# fiberInterface_revC_V3.net
KiCad netlist of a schematic drawn in EAGLE
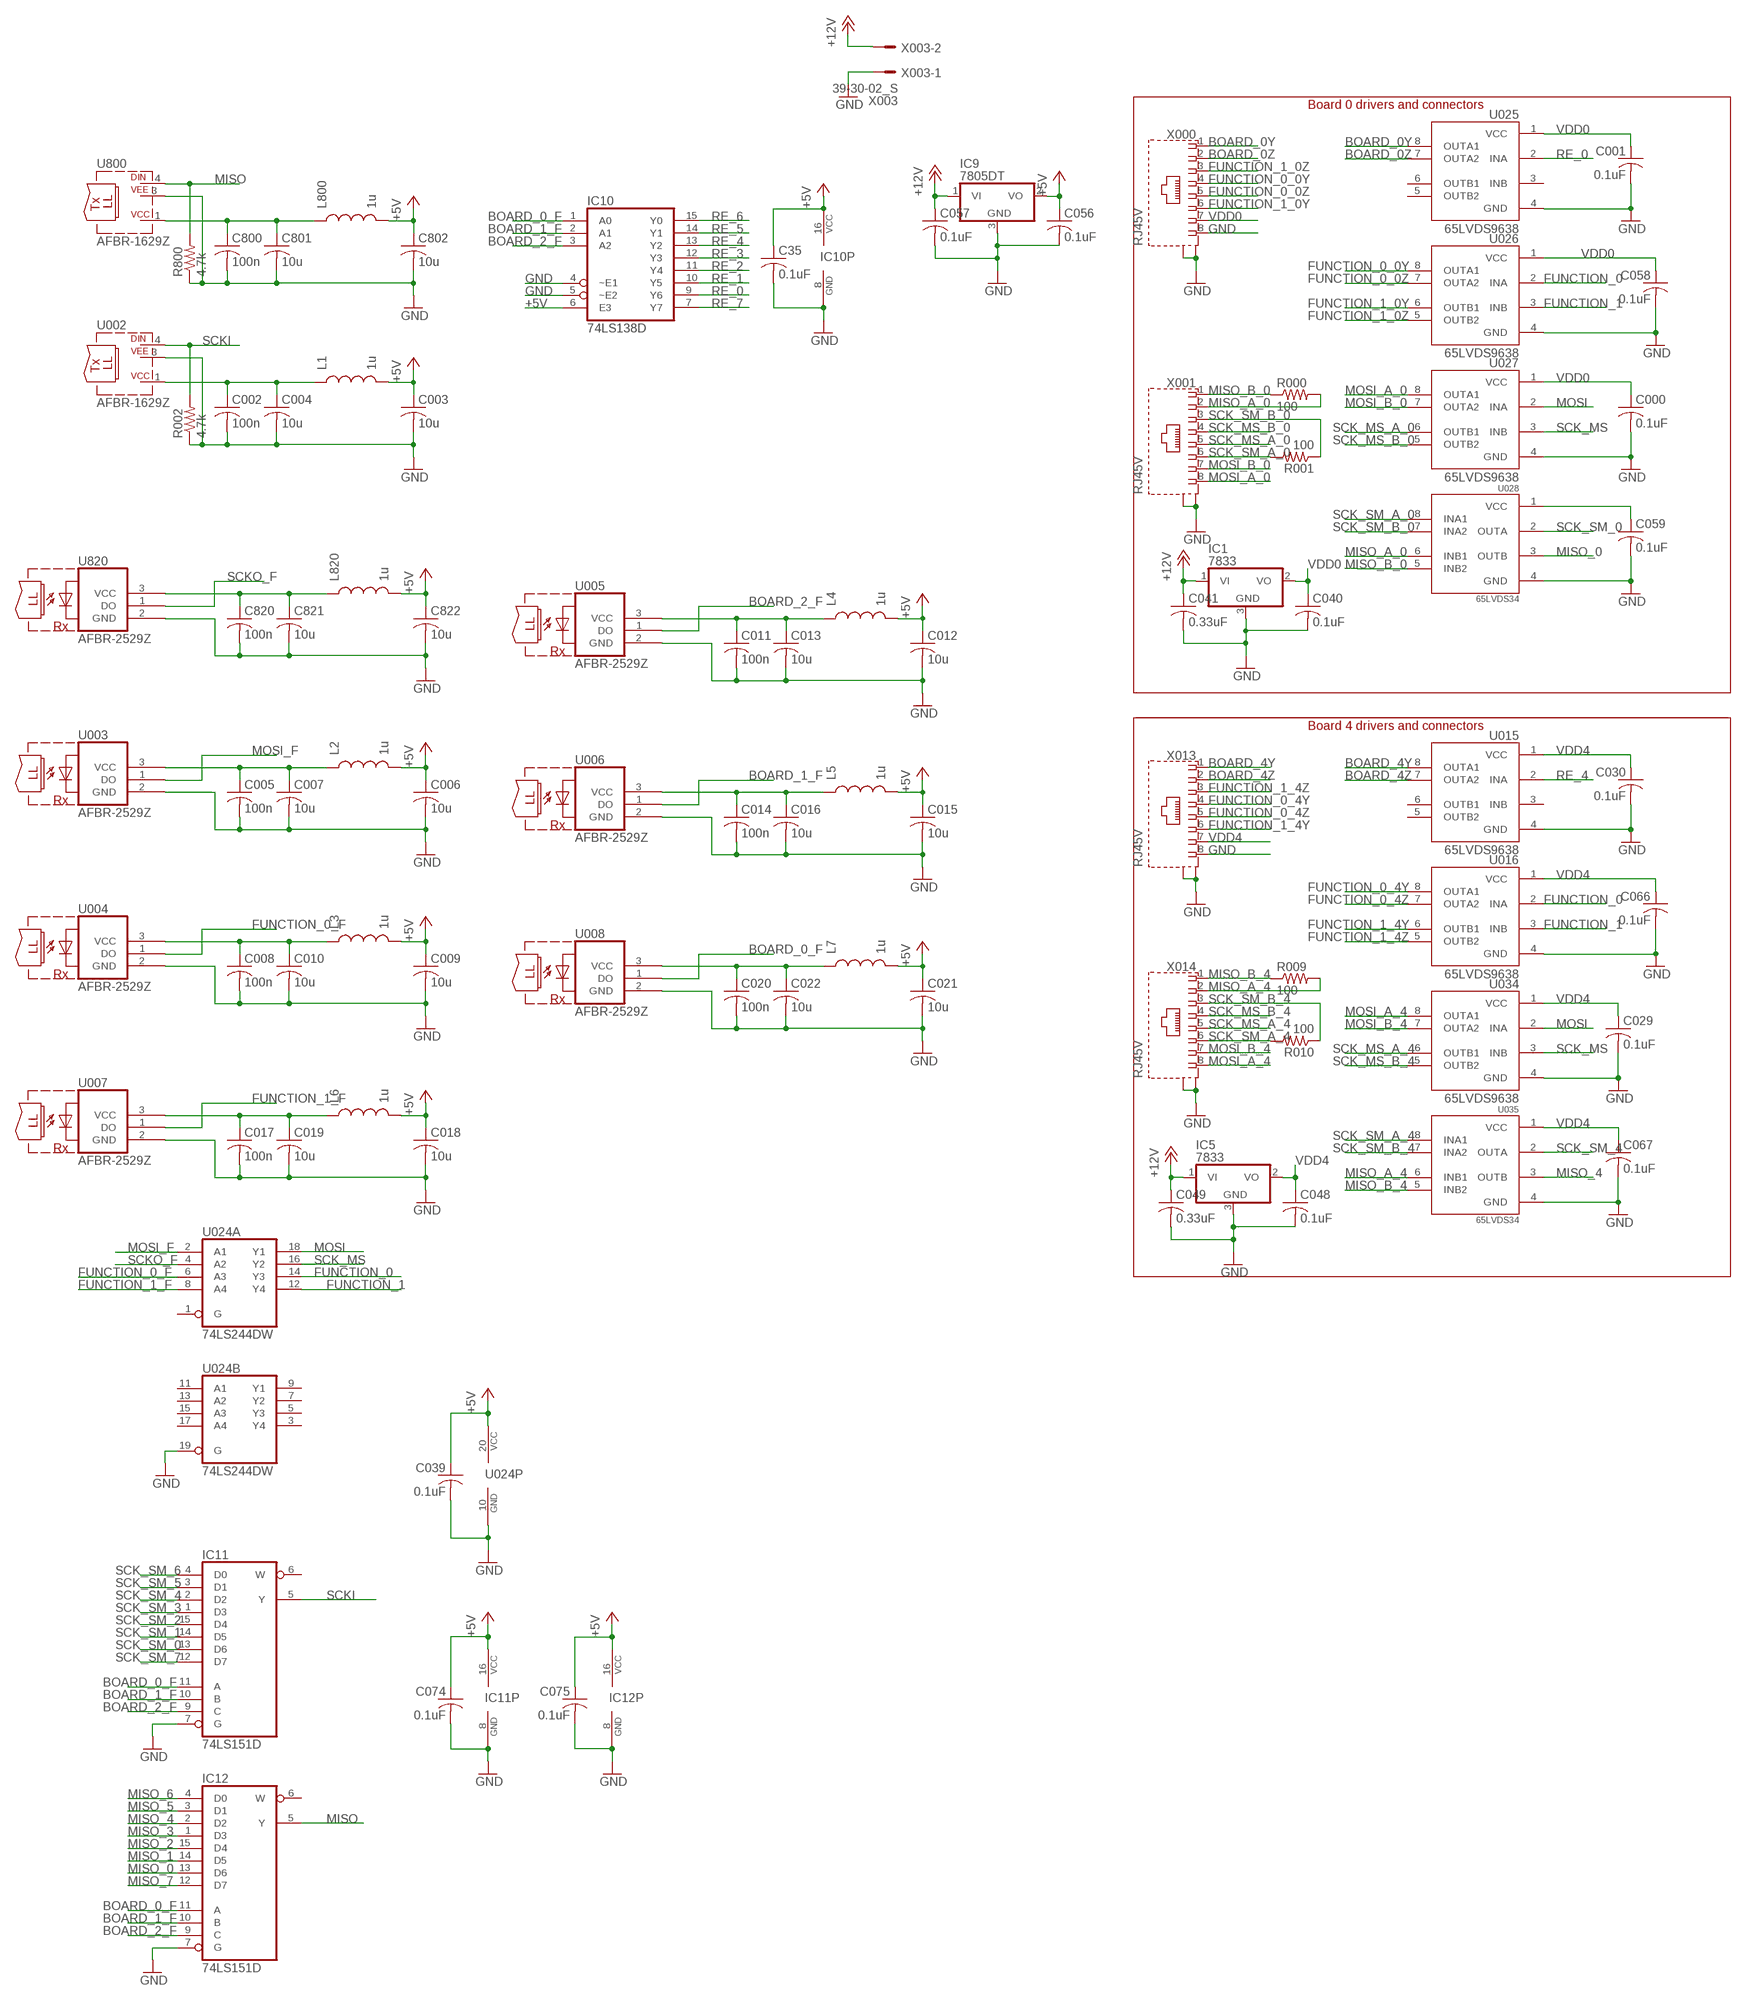
[diagram p0: schematic, sheet 1, part 1 of 2]
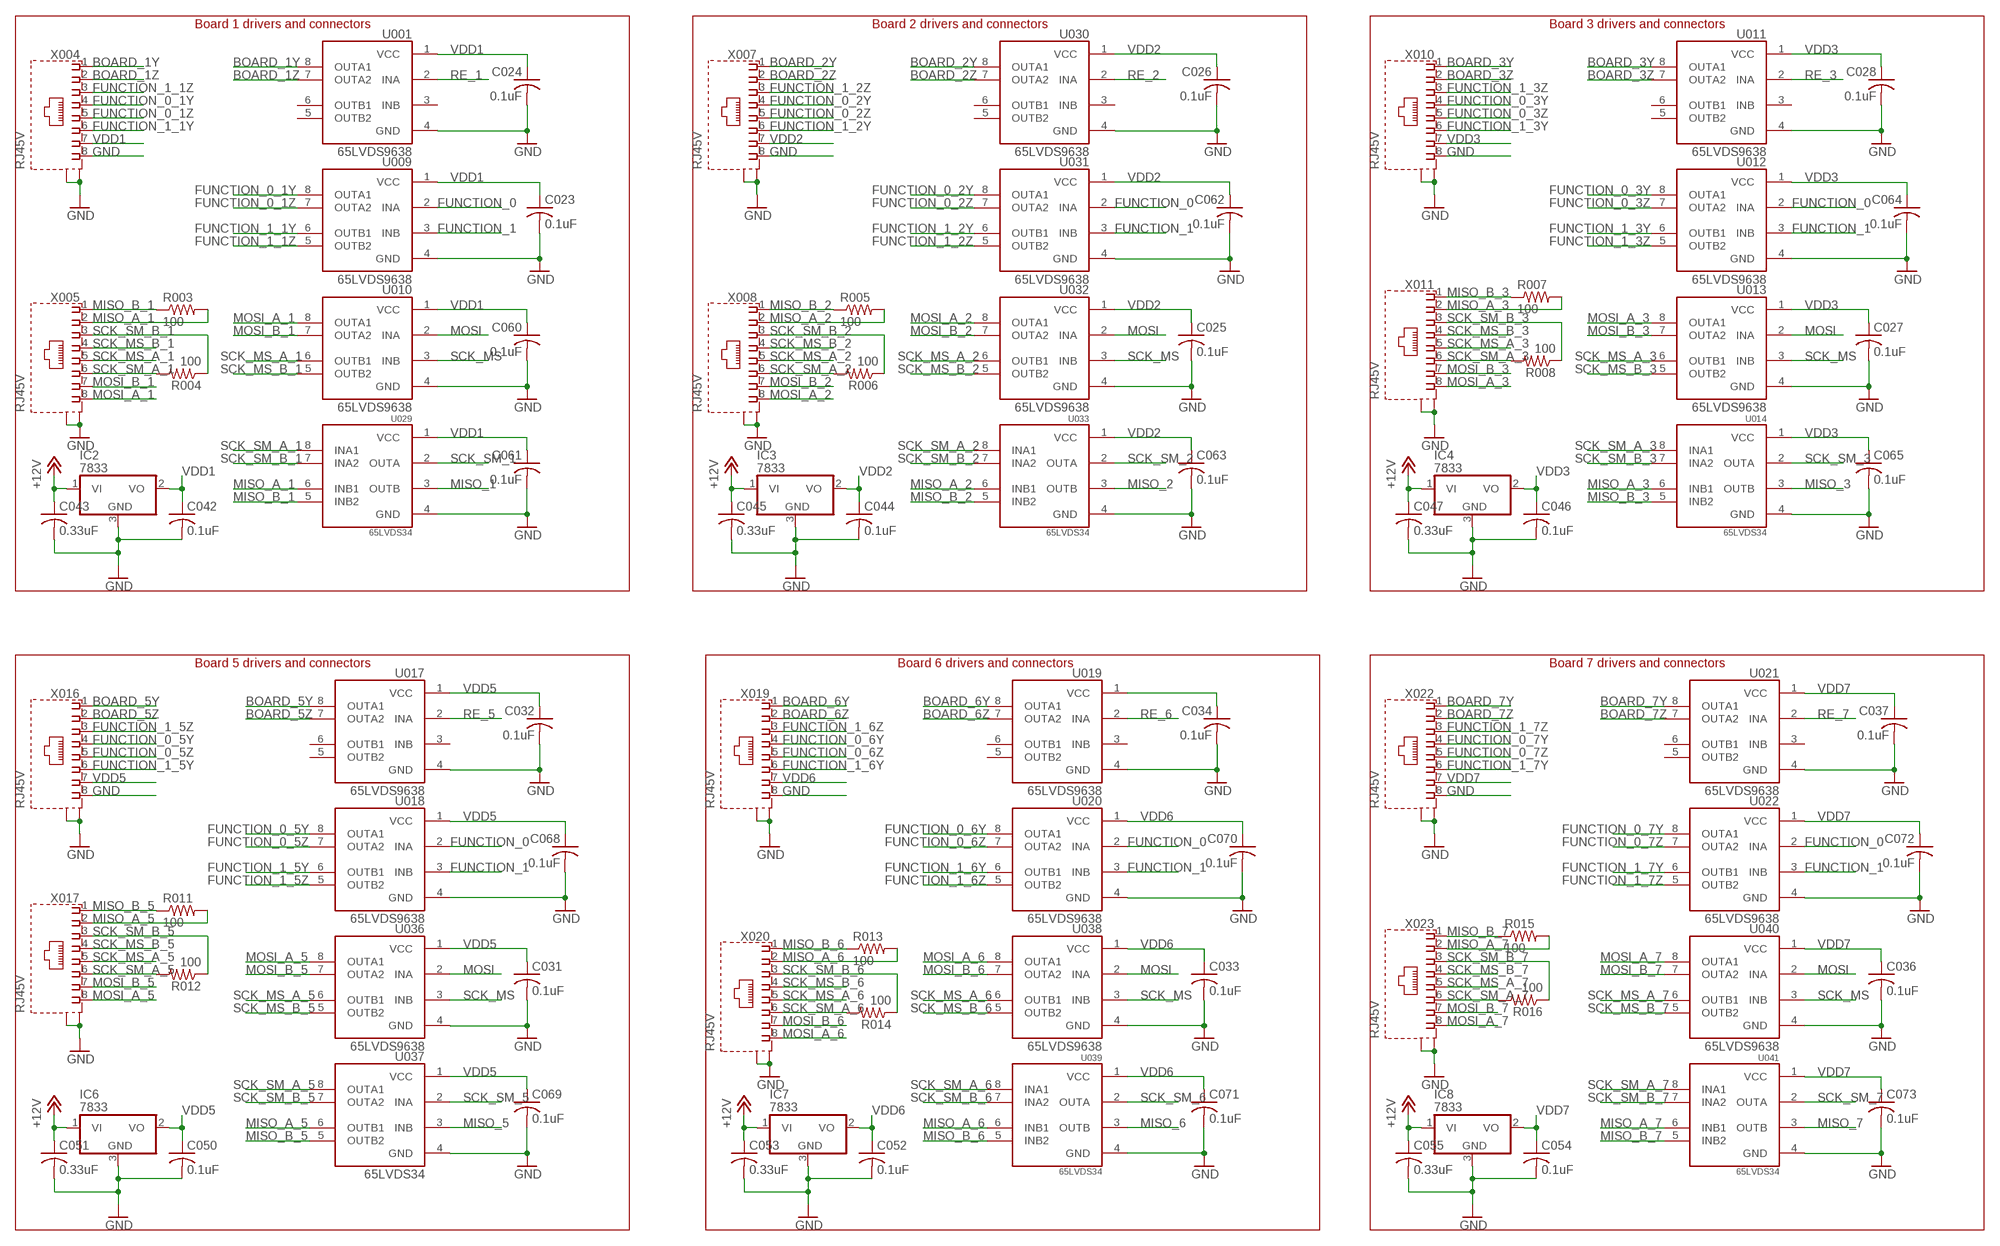
[diagram p1: schematic, sheet 1, part 2 of 2]

(export (version "E")
  (design (tool "Eeschema 10.0.6"))
  (components
    (comp (ref "C000")
      (value "0.1uF")
      (footprint "eagle-import:C0603")
      (libsource (lib "eagle-import") (part "C-USC0603"))
    )
    (comp (ref "C001")
      (value "0.1uF")
      (footprint "eagle-import:C0603")
      (libsource (lib "eagle-import") (part "C-USC0603"))
    )
    (comp (ref "C002")
      (value "100n")
      (footprint "eagle-import:C0805")
      (libsource (lib "eagle-import") (part "C-USC0805"))
    )
    (comp (ref "C003")
      (value "10u")
      (footprint "eagle-import:C1206")
      (libsource (lib "eagle-import") (part "C-USC1206"))
    )
    (comp (ref "C004")
      (value "10u")
      (footprint "eagle-import:C1206")
      (libsource (lib "eagle-import") (part "C-USC1206"))
    )
    (comp (ref "C005")
      (value "100n")
      (footprint "eagle-import:C0805")
      (libsource (lib "eagle-import") (part "C-USC0805"))
    )
    (comp (ref "C006")
      (value "10u")
      (footprint "eagle-import:C1206")
      (libsource (lib "eagle-import") (part "C-USC1206"))
    )
    (comp (ref "C007")
      (value "10u")
      (footprint "eagle-import:C1206")
      (libsource (lib "eagle-import") (part "C-USC1206"))
    )
    (comp (ref "C008")
      (value "100n")
      (footprint "eagle-import:C0805")
      (libsource (lib "eagle-import") (part "C-USC0805"))
    )
    (comp (ref "C009")
      (value "10u")
      (footprint "eagle-import:C1206")
      (libsource (lib "eagle-import") (part "C-USC1206"))
    )
    (comp (ref "C010")
      (value "10u")
      (footprint "eagle-import:C1206")
      (libsource (lib "eagle-import") (part "C-USC1206"))
    )
    (comp (ref "C011")
      (value "100n")
      (footprint "eagle-import:C0805")
      (libsource (lib "eagle-import") (part "C-USC0805"))
    )
    (comp (ref "C012")
      (value "10u")
      (footprint "eagle-import:C1206")
      (libsource (lib "eagle-import") (part "C-USC1206"))
    )
    (comp (ref "C013")
      (value "10u")
      (footprint "eagle-import:C1206")
      (libsource (lib "eagle-import") (part "C-USC1206"))
    )
    (comp (ref "C014")
      (value "100n")
      (footprint "eagle-import:C0805")
      (libsource (lib "eagle-import") (part "C-USC0805"))
    )
    (comp (ref "C015")
      (value "10u")
      (footprint "eagle-import:C1206")
      (libsource (lib "eagle-import") (part "C-USC1206"))
    )
    (comp (ref "C016")
      (value "10u")
      (footprint "eagle-import:C1206")
      (libsource (lib "eagle-import") (part "C-USC1206"))
    )
    (comp (ref "C017")
      (value "100n")
      (footprint "eagle-import:C0805")
      (libsource (lib "eagle-import") (part "C-USC0805"))
    )
    (comp (ref "C018")
      (value "10u")
      (footprint "eagle-import:C1206")
      (libsource (lib "eagle-import") (part "C-USC1206"))
    )
    (comp (ref "C019")
      (value "10u")
      (footprint "eagle-import:C1206")
      (libsource (lib "eagle-import") (part "C-USC1206"))
    )
    (comp (ref "C020")
      (value "100n")
      (footprint "eagle-import:C0805")
      (libsource (lib "eagle-import") (part "C-USC0805"))
    )
    (comp (ref "C021")
      (value "10u")
      (footprint "eagle-import:C1206")
      (libsource (lib "eagle-import") (part "C-USC1206"))
    )
    (comp (ref "C022")
      (value "10u")
      (footprint "eagle-import:C1206")
      (libsource (lib "eagle-import") (part "C-USC1206"))
    )
    (comp (ref "C023")
      (value "0.1uF")
      (footprint "eagle-import:C0603")
      (libsource (lib "eagle-import") (part "C-USC0603"))
    )
    (comp (ref "C024")
      (value "0.1uF")
      (footprint "eagle-import:C0603")
      (libsource (lib "eagle-import") (part "C-USC0603"))
    )
    (comp (ref "C025")
      (value "0.1uF")
      (footprint "eagle-import:C0603")
      (libsource (lib "eagle-import") (part "C-USC0603"))
    )
    (comp (ref "C026")
      (value "0.1uF")
      (footprint "eagle-import:C0603")
      (libsource (lib "eagle-import") (part "C-USC0603"))
    )
    (comp (ref "C027")
      (value "0.1uF")
      (footprint "eagle-import:C0603")
      (libsource (lib "eagle-import") (part "C-USC0603"))
    )
    (comp (ref "C028")
      (value "0.1uF")
      (footprint "eagle-import:C0603")
      (libsource (lib "eagle-import") (part "C-USC0603"))
    )
    (comp (ref "C029")
      (value "0.1uF")
      (footprint "eagle-import:C0603")
      (libsource (lib "eagle-import") (part "C-USC0603"))
    )
    (comp (ref "C030")
      (value "0.1uF")
      (footprint "eagle-import:C0603")
      (libsource (lib "eagle-import") (part "C-USC0603"))
    )
    (comp (ref "C031")
      (value "0.1uF")
      (footprint "eagle-import:C0603")
      (libsource (lib "eagle-import") (part "C-USC0603"))
    )
    (comp (ref "C032")
      (value "0.1uF")
      (footprint "eagle-import:C0603")
      (libsource (lib "eagle-import") (part "C-USC0603"))
    )
    (comp (ref "C033")
      (value "0.1uF")
      (footprint "eagle-import:C0603")
      (libsource (lib "eagle-import") (part "C-USC0603"))
    )
    (comp (ref "C034")
      (value "0.1uF")
      (footprint "eagle-import:C0603")
      (libsource (lib "eagle-import") (part "C-USC0603"))
    )
    (comp (ref "C35")
      (value "0.1uF")
      (footprint "eagle-import:C0603")
      (libsource (lib "eagle-import") (part "C-USC0603"))
    )
    (comp (ref "C036")
      (value "0.1uF")
      (footprint "eagle-import:C0603")
      (libsource (lib "eagle-import") (part "C-USC0603"))
    )
    (comp (ref "C037")
      (value "0.1uF")
      (footprint "eagle-import:C0603")
      (libsource (lib "eagle-import") (part "C-USC0603"))
    )
    (comp (ref "C039")
      (value "0.1uF")
      (footprint "eagle-import:C0603")
      (libsource (lib "eagle-import") (part "C-USC0603"))
    )
    (comp (ref "C040")
      (value "0.1uF")
      (footprint "eagle-import:C0805")
      (libsource (lib "eagle-import") (part "C-USC0805"))
    )
    (comp (ref "C041")
      (value "0.33uF")
      (footprint "eagle-import:C0805")
      (libsource (lib "eagle-import") (part "C-USC0805"))
    )
    (comp (ref "C042")
      (value "0.1uF")
      (footprint "eagle-import:C0805")
      (libsource (lib "eagle-import") (part "C-USC0805"))
    )
    (comp (ref "C043")
      (value "0.33uF")
      (footprint "eagle-import:C0805")
      (libsource (lib "eagle-import") (part "C-USC0805"))
    )
    (comp (ref "C044")
      (value "0.1uF")
      (footprint "eagle-import:C0805")
      (libsource (lib "eagle-import") (part "C-USC0805"))
    )
    (comp (ref "C045")
      (value "0.33uF")
      (footprint "eagle-import:C0805")
      (libsource (lib "eagle-import") (part "C-USC0805"))
    )
    (comp (ref "C046")
      (value "0.1uF")
      (footprint "eagle-import:C0805")
      (libsource (lib "eagle-import") (part "C-USC0805"))
    )
    (comp (ref "C047")
      (value "0.33uF")
      (footprint "eagle-import:C0805")
      (libsource (lib "eagle-import") (part "C-USC0805"))
    )
    (comp (ref "C048")
      (value "0.1uF")
      (footprint "eagle-import:C0805")
      (libsource (lib "eagle-import") (part "C-USC0805"))
    )
    (comp (ref "C049")
      (value "0.33uF")
      (footprint "eagle-import:C0805")
      (libsource (lib "eagle-import") (part "C-USC0805"))
    )
    (comp (ref "C050")
      (value "0.1uF")
      (footprint "eagle-import:C0805")
      (libsource (lib "eagle-import") (part "C-USC0805"))
    )
    (comp (ref "C051")
      (value "0.33uF")
      (footprint "eagle-import:C0805")
      (libsource (lib "eagle-import") (part "C-USC0805"))
    )
    (comp (ref "C052")
      (value "0.1uF")
      (footprint "eagle-import:C0805")
      (libsource (lib "eagle-import") (part "C-USC0805"))
    )
    (comp (ref "C053")
      (value "0.33uF")
      (footprint "eagle-import:C0805")
      (libsource (lib "eagle-import") (part "C-USC0805"))
    )
    (comp (ref "C054")
      (value "0.1uF")
      (footprint "eagle-import:C0805")
      (libsource (lib "eagle-import") (part "C-USC0805"))
    )
    (comp (ref "C055")
      (value "0.33uF")
      (footprint "eagle-import:C0805")
      (libsource (lib "eagle-import") (part "C-USC0805"))
    )
    (comp (ref "C056")
      (value "0.1uF")
      (footprint "eagle-import:C0603")
      (libsource (lib "eagle-import") (part "C-USC0603"))
    )
    (comp (ref "C057")
      (value "0.1uF")
      (footprint "eagle-import:C0603")
      (libsource (lib "eagle-import") (part "C-USC0603"))
    )
    (comp (ref "C058")
      (value "0.1uF")
      (footprint "eagle-import:C0603")
      (libsource (lib "eagle-import") (part "C-USC0603"))
    )
    (comp (ref "C059")
      (value "0.1uF")
      (footprint "eagle-import:C0603")
      (libsource (lib "eagle-import") (part "C-USC0603"))
    )
    (comp (ref "C060")
      (value "0.1uF")
      (footprint "eagle-import:C0603")
      (libsource (lib "eagle-import") (part "C-USC0603"))
    )
    (comp (ref "C061")
      (value "0.1uF")
      (footprint "eagle-import:C0603")
      (libsource (lib "eagle-import") (part "C-USC0603"))
    )
    (comp (ref "C062")
      (value "0.1uF")
      (footprint "eagle-import:C0603")
      (libsource (lib "eagle-import") (part "C-USC0603"))
    )
    (comp (ref "C063")
      (value "0.1uF")
      (footprint "eagle-import:C0603")
      (libsource (lib "eagle-import") (part "C-USC0603"))
    )
    (comp (ref "C064")
      (value "0.1uF")
      (footprint "eagle-import:C0603")
      (libsource (lib "eagle-import") (part "C-USC0603"))
    )
    (comp (ref "C065")
      (value "0.1uF")
      (footprint "eagle-import:C0603")
      (libsource (lib "eagle-import") (part "C-USC0603"))
    )
    (comp (ref "C066")
      (value "0.1uF")
      (footprint "eagle-import:C0603")
      (libsource (lib "eagle-import") (part "C-USC0603"))
    )
    (comp (ref "C067")
      (value "0.1uF")
      (footprint "eagle-import:C0603")
      (libsource (lib "eagle-import") (part "C-USC0603"))
    )
    (comp (ref "C068")
      (value "0.1uF")
      (footprint "eagle-import:C0603")
      (libsource (lib "eagle-import") (part "C-USC0603"))
    )
    (comp (ref "C069")
      (value "0.1uF")
      (footprint "eagle-import:C0603")
      (libsource (lib "eagle-import") (part "C-USC0603"))
    )
    (comp (ref "C070")
      (value "0.1uF")
      (footprint "eagle-import:C0603")
      (libsource (lib "eagle-import") (part "C-USC0603"))
    )
    (comp (ref "C071")
      (value "0.1uF")
      (footprint "eagle-import:C0603")
      (libsource (lib "eagle-import") (part "C-USC0603"))
    )
    (comp (ref "C072")
      (value "0.1uF")
      (footprint "eagle-import:C0603")
      (libsource (lib "eagle-import") (part "C-USC0603"))
    )
    (comp (ref "C073")
      (value "0.1uF")
      (footprint "eagle-import:C0603")
      (libsource (lib "eagle-import") (part "C-USC0603"))
    )
    (comp (ref "C074")
      (value "0.1uF")
      (footprint "eagle-import:C0603")
      (libsource (lib "eagle-import") (part "C-USC0603"))
    )
    (comp (ref "C075")
      (value "0.1uF")
      (footprint "eagle-import:C0603")
      (libsource (lib "eagle-import") (part "C-USC0603"))
    )
    (comp (ref "C800")
      (value "100n")
      (footprint "eagle-import:C0805")
      (libsource (lib "eagle-import") (part "C-USC0805"))
    )
    (comp (ref "C801")
      (value "10u")
      (footprint "eagle-import:C1206")
      (libsource (lib "eagle-import") (part "C-USC1206"))
    )
    (comp (ref "C802")
      (value "10u")
      (footprint "eagle-import:C1206")
      (libsource (lib "eagle-import") (part "C-USC1206"))
    )
    (comp (ref "C820")
      (value "100n")
      (footprint "eagle-import:C0805")
      (libsource (lib "eagle-import") (part "C-USC0805"))
    )
    (comp (ref "C821")
      (value "10u")
      (footprint "eagle-import:C1206")
      (libsource (lib "eagle-import") (part "C-USC1206"))
    )
    (comp (ref "C822")
      (value "10u")
      (footprint "eagle-import:C1206")
      (libsource (lib "eagle-import") (part "C-USC1206"))
    )
    (comp (ref "IC1")
      (value "7833")
      (footprint "eagle-import:TO252")
      (libsource (lib "eagle-import") (part "78DT05"))
    )
    (comp (ref "IC2")
      (value "7833")
      (footprint "eagle-import:TO252")
      (libsource (lib "eagle-import") (part "78DT05"))
    )
    (comp (ref "IC3")
      (value "7833")
      (footprint "eagle-import:TO252")
      (libsource (lib "eagle-import") (part "78DT05"))
    )
    (comp (ref "IC4")
      (value "7833")
      (footprint "eagle-import:TO252")
      (libsource (lib "eagle-import") (part "78DT05"))
    )
    (comp (ref "IC5")
      (value "7833")
      (footprint "eagle-import:TO252")
      (libsource (lib "eagle-import") (part "78DT05"))
    )
    (comp (ref "IC6")
      (value "7833")
      (footprint "eagle-import:TO252")
      (libsource (lib "eagle-import") (part "78DT05"))
    )
    (comp (ref "IC7")
      (value "7833")
      (footprint "eagle-import:TO252")
      (libsource (lib "eagle-import") (part "78DT05"))
    )
    (comp (ref "IC8")
      (value "7833")
      (footprint "eagle-import:TO252")
      (libsource (lib "eagle-import") (part "78DT05"))
    )
    (comp (ref "IC9")
      (value "7805DT")
      (footprint "eagle-import:TO252")
      (libsource (lib "eagle-import") (part "78DT05"))
    )
    (comp (ref "IC10")
      (value "74LS138D")
      (footprint "eagle-import:SO16")
      (libsource (lib "eagle-import") (part "74238DLS"))
    )
    (comp (ref "IC11")
      (value "74LS151D")
      (footprint "eagle-import:SO16")
      (libsource (lib "eagle-import") (part "74151DLS"))
    )
    (comp (ref "IC12")
      (value "74LS151D")
      (footprint "eagle-import:SO16")
      (libsource (lib "eagle-import") (part "74151DLS"))
    )
    (comp (ref "L1")
      (value "1u")
      (footprint "eagle-import:0805")
      (libsource (lib "eagle-import") (part "INDUCTOR0805"))
    )
    (comp (ref "L2")
      (value "1u")
      (footprint "eagle-import:0805")
      (libsource (lib "eagle-import") (part "INDUCTOR0805"))
    )
    (comp (ref "L3")
      (value "1u")
      (footprint "eagle-import:0805")
      (libsource (lib "eagle-import") (part "INDUCTOR0805"))
    )
    (comp (ref "L4")
      (value "1u")
      (footprint "eagle-import:0805")
      (libsource (lib "eagle-import") (part "INDUCTOR0805"))
    )
    (comp (ref "L5")
      (value "1u")
      (footprint "eagle-import:0805")
      (libsource (lib "eagle-import") (part "INDUCTOR0805"))
    )
    (comp (ref "L6")
      (value "1u")
      (footprint "eagle-import:0805")
      (libsource (lib "eagle-import") (part "INDUCTOR0805"))
    )
    (comp (ref "L7")
      (value "1u")
      (footprint "eagle-import:0805")
      (libsource (lib "eagle-import") (part "INDUCTOR0805"))
    )
    (comp (ref "L800")
      (value "1u")
      (footprint "eagle-import:0805")
      (libsource (lib "eagle-import") (part "INDUCTOR0805"))
    )
    (comp (ref "L820")
      (value "1u")
      (footprint "eagle-import:0805")
      (libsource (lib "eagle-import") (part "INDUCTOR0805"))
    )
    (comp (ref "R000")
      (value "100")
      (footprint "eagle-import:R0805")
      (libsource (lib "eagle-import") (part "R-US_R0805"))
    )
    (comp (ref "R001")
      (value "100")
      (footprint "eagle-import:R0805")
      (libsource (lib "eagle-import") (part "R-US_R0805"))
    )
    (comp (ref "R002")
      (value "4.7k")
      (footprint "eagle-import:R0805")
      (libsource (lib "eagle-import") (part "R-US_R0805"))
    )
    (comp (ref "R003")
      (value "100")
      (footprint "eagle-import:R0805")
      (libsource (lib "eagle-import") (part "R-US_R0805"))
    )
    (comp (ref "R004")
      (value "100")
      (footprint "eagle-import:R0805")
      (libsource (lib "eagle-import") (part "R-US_R0805"))
    )
    (comp (ref "R005")
      (value "100")
      (footprint "eagle-import:R0805")
      (libsource (lib "eagle-import") (part "R-US_R0805"))
    )
    (comp (ref "R006")
      (value "100")
      (footprint "eagle-import:R0805")
      (libsource (lib "eagle-import") (part "R-US_R0805"))
    )
    (comp (ref "R007")
      (value "100")
      (footprint "eagle-import:R0805")
      (libsource (lib "eagle-import") (part "R-US_R0805"))
    )
    (comp (ref "R008")
      (value "100")
      (footprint "eagle-import:R0805")
      (libsource (lib "eagle-import") (part "R-US_R0805"))
    )
    (comp (ref "R009")
      (value "100")
      (footprint "eagle-import:R0805")
      (libsource (lib "eagle-import") (part "R-US_R0805"))
    )
    (comp (ref "R010")
      (value "100")
      (footprint "eagle-import:R0805")
      (libsource (lib "eagle-import") (part "R-US_R0805"))
    )
    (comp (ref "R011")
      (value "100")
      (footprint "eagle-import:R0805")
      (libsource (lib "eagle-import") (part "R-US_R0805"))
    )
    (comp (ref "R012")
      (value "100")
      (footprint "eagle-import:R0805")
      (libsource (lib "eagle-import") (part "R-US_R0805"))
    )
    (comp (ref "R013")
      (value "100")
      (footprint "eagle-import:R0805")
      (libsource (lib "eagle-import") (part "R-US_R0805"))
    )
    (comp (ref "R014")
      (value "100")
      (footprint "eagle-import:R0805")
      (libsource (lib "eagle-import") (part "R-US_R0805"))
    )
    (comp (ref "R015")
      (value "100")
      (footprint "eagle-import:R0805")
      (libsource (lib "eagle-import") (part "R-US_R0805"))
    )
    (comp (ref "R016")
      (value "100")
      (footprint "eagle-import:R0805")
      (libsource (lib "eagle-import") (part "R-US_R0805"))
    )
    (comp (ref "R800")
      (value "4.7k")
      (footprint "eagle-import:R0805")
      (libsource (lib "eagle-import") (part "R-US_R0805"))
    )
    (comp (ref "U001")
      (value "65LVDS9638")
      (footprint "eagle-import:SO08-1")
      (libsource (lib "eagle-import") (part "DS9638"))
    )
    (comp (ref "U002")
      (value "AFBR-1629Z")
      (footprint "eagle-import:HFBR-15X3")
      (libsource (lib "eagle-import") (part "AFBR-16XXZ"))
    )
    (comp (ref "U003")
      (value "AFBR-2529Z")
      (footprint "eagle-import:HFBR-15X3")
      (libsource (lib "eagle-import") (part "AFBR-26X4Z"))
    )
    (comp (ref "U004")
      (value "AFBR-2529Z")
      (footprint "eagle-import:HFBR-15X3")
      (libsource (lib "eagle-import") (part "AFBR-26X4Z"))
    )
    (comp (ref "U005")
      (value "AFBR-2529Z")
      (footprint "eagle-import:HFBR-15X3")
      (libsource (lib "eagle-import") (part "AFBR-26X4Z"))
    )
    (comp (ref "U006")
      (value "AFBR-2529Z")
      (footprint "eagle-import:HFBR-15X3")
      (libsource (lib "eagle-import") (part "AFBR-26X4Z"))
    )
    (comp (ref "U007")
      (value "AFBR-2529Z")
      (footprint "eagle-import:HFBR-15X3")
      (libsource (lib "eagle-import") (part "AFBR-26X4Z"))
    )
    (comp (ref "U008")
      (value "AFBR-2529Z")
      (footprint "eagle-import:HFBR-15X3")
      (libsource (lib "eagle-import") (part "AFBR-26X4Z"))
    )
    (comp (ref "U009")
      (value "65LVDS9638")
      (footprint "eagle-import:SO08-1")
      (libsource (lib "eagle-import") (part "DS9638"))
    )
    (comp (ref "U010")
      (value "65LVDS9638")
      (footprint "eagle-import:SO08-1")
      (libsource (lib "eagle-import") (part "DS9638"))
    )
    (comp (ref "U011")
      (value "65LVDS9638")
      (footprint "eagle-import:SO08-1")
      (libsource (lib "eagle-import") (part "DS9638"))
    )
    (comp (ref "U012")
      (value "65LVDS9638")
      (footprint "eagle-import:SO08-1")
      (libsource (lib "eagle-import") (part "DS9638"))
    )
    (comp (ref "U013")
      (value "65LVDS9638")
      (footprint "eagle-import:SO08-1")
      (libsource (lib "eagle-import") (part "DS9638"))
    )
    (comp (ref "U014")
      (value "65LVDS34")
      (footprint "eagle-import:SO08-1")
      (libsource (lib "eagle-import") (part "DS9637A"))
    )
    (comp (ref "U015")
      (value "65LVDS9638")
      (footprint "eagle-import:SO08-1")
      (libsource (lib "eagle-import") (part "DS9638"))
    )
    (comp (ref "U016")
      (value "65LVDS9638")
      (footprint "eagle-import:SO08-1")
      (libsource (lib "eagle-import") (part "DS9638"))
    )
    (comp (ref "U017")
      (value "65LVDS9638")
      (footprint "eagle-import:SO08-1")
      (libsource (lib "eagle-import") (part "DS9638"))
    )
    (comp (ref "U018")
      (value "65LVDS9638")
      (footprint "eagle-import:SO08-1")
      (libsource (lib "eagle-import") (part "DS9638"))
    )
    (comp (ref "U019")
      (value "65LVDS9638")
      (footprint "eagle-import:SO08-1")
      (libsource (lib "eagle-import") (part "DS9638"))
    )
    (comp (ref "U020")
      (value "65LVDS9638")
      (footprint "eagle-import:SO08-1")
      (libsource (lib "eagle-import") (part "DS9638"))
    )
    (comp (ref "U021")
      (value "65LVDS9638")
      (footprint "eagle-import:SO08-1")
      (libsource (lib "eagle-import") (part "DS9638"))
    )
    (comp (ref "U022")
      (value "65LVDS9638")
      (footprint "eagle-import:SO08-1")
      (libsource (lib "eagle-import") (part "DS9638"))
    )
    (comp (ref "U024")
      (value "74LS244DW")
      (footprint "eagle-import:SO20W")
      (libsource (lib "eagle-import") (part "74244DWLS"))
    )
    (comp (ref "U025")
      (value "65LVDS9638")
      (footprint "eagle-import:SO08-1")
      (libsource (lib "eagle-import") (part "DS9638"))
    )
    (comp (ref "U026")
      (value "65LVDS9638")
      (footprint "eagle-import:SO08-1")
      (libsource (lib "eagle-import") (part "DS9638"))
    )
    (comp (ref "U027")
      (value "65LVDS9638")
      (footprint "eagle-import:SO08-1")
      (libsource (lib "eagle-import") (part "DS9638"))
    )
    (comp (ref "U028")
      (value "65LVDS34")
      (footprint "eagle-import:SO08-1")
      (libsource (lib "eagle-import") (part "DS9637A"))
    )
    (comp (ref "U029")
      (value "65LVDS34")
      (footprint "eagle-import:SO08-1")
      (libsource (lib "eagle-import") (part "DS9637A"))
    )
    (comp (ref "U030")
      (value "65LVDS9638")
      (footprint "eagle-import:SO08-1")
      (libsource (lib "eagle-import") (part "DS9638"))
    )
    (comp (ref "U031")
      (value "65LVDS9638")
      (footprint "eagle-import:SO08-1")
      (libsource (lib "eagle-import") (part "DS9638"))
    )
    (comp (ref "U032")
      (value "65LVDS9638")
      (footprint "eagle-import:SO08-1")
      (libsource (lib "eagle-import") (part "DS9638"))
    )
    (comp (ref "U033")
      (value "65LVDS34")
      (footprint "eagle-import:SO08-1")
      (libsource (lib "eagle-import") (part "DS9637A"))
    )
    (comp (ref "U034")
      (value "65LVDS9638")
      (footprint "eagle-import:SO08-1")
      (libsource (lib "eagle-import") (part "DS9638"))
    )
    (comp (ref "U035")
      (value "65LVDS34")
      (footprint "eagle-import:SO08-1")
      (libsource (lib "eagle-import") (part "DS9637A"))
    )
    (comp (ref "U036")
      (value "65LVDS9638")
      (footprint "eagle-import:SO08-1")
      (libsource (lib "eagle-import") (part "DS9638"))
    )
    (comp (ref "U037")
      (value "65LVDS34")
      (footprint "eagle-import:SO08-1")
      (libsource (lib "eagle-import") (part "DS9638"))
    )
    (comp (ref "U038")
      (value "65LVDS9638")
      (footprint "eagle-import:SO08-1")
      (libsource (lib "eagle-import") (part "DS9638"))
    )
    (comp (ref "U039")
      (value "65LVDS34")
      (footprint "eagle-import:SO08-1")
      (libsource (lib "eagle-import") (part "DS9637A"))
    )
    (comp (ref "U040")
      (value "65LVDS9638")
      (footprint "eagle-import:SO08-1")
      (libsource (lib "eagle-import") (part "DS9638"))
    )
    (comp (ref "U041")
      (value "65LVDS34")
      (footprint "eagle-import:SO08-1")
      (libsource (lib "eagle-import") (part "DS9637A"))
    )
    (comp (ref "U800")
      (value "AFBR-1629Z")
      (footprint "eagle-import:HFBR-15X3")
      (libsource (lib "eagle-import") (part "AFBR-16XXZ"))
    )
    (comp (ref "U820")
      (value "AFBR-2529Z")
      (footprint "eagle-import:HFBR-15X3")
      (libsource (lib "eagle-import") (part "AFBR-26X4Z"))
    )
    (comp (ref "X000")
      (value "RJ45V")
      (footprint "eagle-import:RJ45-VERTICAL")
      (libsource (lib "eagle-import") (part "RJ45V"))
    )
    (comp (ref "X001")
      (value "RJ45V")
      (footprint "eagle-import:RJ45-VERTICAL")
      (libsource (lib "eagle-import") (part "RJ45V"))
    )
    (comp (ref "X003")
      (value "39-30-02_S")
      (footprint "eagle-import:39-30-_02_")
      (libsource (lib "eagle-import") (part "39-30-?02?_S"))
    )
    (comp (ref "X004")
      (value "RJ45V")
      (footprint "eagle-import:RJ45-VERTICAL")
      (libsource (lib "eagle-import") (part "RJ45V"))
    )
    (comp (ref "X005")
      (value "RJ45V")
      (footprint "eagle-import:RJ45-VERTICAL")
      (libsource (lib "eagle-import") (part "RJ45V"))
    )
    (comp (ref "X007")
      (value "RJ45V")
      (footprint "eagle-import:RJ45-VERTICAL")
      (libsource (lib "eagle-import") (part "RJ45V"))
    )
    (comp (ref "X008")
      (value "RJ45V")
      (footprint "eagle-import:RJ45-VERTICAL")
      (libsource (lib "eagle-import") (part "RJ45V"))
    )
    (comp (ref "X010")
      (value "RJ45V")
      (footprint "eagle-import:RJ45-VERTICAL")
      (libsource (lib "eagle-import") (part "RJ45V"))
    )
    (comp (ref "X011")
      (value "RJ45V")
      (footprint "eagle-import:RJ45-VERTICAL")
      (libsource (lib "eagle-import") (part "RJ45V"))
    )
    (comp (ref "X013")
      (value "RJ45V")
      (footprint "eagle-import:RJ45-VERTICAL")
      (libsource (lib "eagle-import") (part "RJ45V"))
    )
    (comp (ref "X014")
      (value "RJ45V")
      (footprint "eagle-import:RJ45-VERTICAL")
      (libsource (lib "eagle-import") (part "RJ45V"))
    )
    (comp (ref "X016")
      (value "RJ45V")
      (footprint "eagle-import:RJ45-VERTICAL")
      (libsource (lib "eagle-import") (part "RJ45V"))
    )
    (comp (ref "X017")
      (value "RJ45V")
      (footprint "eagle-import:RJ45-VERTICAL")
      (libsource (lib "eagle-import") (part "RJ45V"))
    )
    (comp (ref "X019")
      (value "RJ45V")
      (footprint "eagle-import:RJ45-VERTICAL")
      (libsource (lib "eagle-import") (part "RJ45V"))
    )
    (comp (ref "X020")
      (value "RJ45V")
      (footprint "eagle-import:RJ45-VERTICAL")
      (libsource (lib "eagle-import") (part "RJ45V"))
    )
    (comp (ref "X022")
      (value "RJ45V")
      (footprint "eagle-import:RJ45-VERTICAL")
      (libsource (lib "eagle-import") (part "RJ45V"))
    )
    (comp (ref "X023")
      (value "RJ45V")
      (footprint "eagle-import:RJ45-VERTICAL")
      (libsource (lib "eagle-import") (part "RJ45V"))
    )
  )
  (nets
    (net (code "1") (name "+5V") (class "Default")
      (node (ref "C003") (pin "1") (pinfunction "1_1") (pintype "passive"))
      (node (ref "C006") (pin "1") (pinfunction "1_1") (pintype "passive"))
      (node (ref "C009") (pin "1") (pinfunction "1_1") (pintype "passive"))
      (node (ref "C012") (pin "1") (pinfunction "1_1") (pintype "passive"))
      (node (ref "C015") (pin "1") (pinfunction "1_1") (pintype "passive"))
      (node (ref "C018") (pin "1") (pinfunction "1_1") (pintype "passive"))
      (node (ref "C021") (pin "1") (pinfunction "1_1") (pintype "passive"))
      (node (ref "C039") (pin "1") (pinfunction "1_1") (pintype "passive"))
      (node (ref "C056") (pin "1") (pinfunction "1_1") (pintype "passive"))
      (node (ref "C074") (pin "1") (pinfunction "1_1") (pintype "passive"))
      (node (ref "C075") (pin "1") (pinfunction "1_1") (pintype "passive"))
      (node (ref "C35") (pin "1") (pinfunction "1_1") (pintype "passive"))
      (node (ref "C802") (pin "1") (pinfunction "1_1") (pintype "passive"))
      (node (ref "C822") (pin "1") (pinfunction "1_1") (pintype "passive"))
      (node (ref "IC10") (pin "16") (pinfunction "VCC_16") (pintype "power_in"))
      (node (ref "IC10") (pin "6") (pinfunction "E3_6") (pintype "input"))
      (node (ref "IC11") (pin "16") (pinfunction "VCC_16") (pintype "power_in"))
      (node (ref "IC12") (pin "16") (pinfunction "VCC_16") (pintype "power_in"))
      (node (ref "IC9") (pin "2") (pinfunction "VO_2") (pintype "passive"))
      (node (ref "L1") (pin "2") (pinfunction "2_2") (pintype "passive"))
      (node (ref "L2") (pin "2") (pinfunction "2_2") (pintype "passive"))
      (node (ref "L3") (pin "2") (pinfunction "2_2") (pintype "passive"))
      (node (ref "L4") (pin "2") (pinfunction "2_2") (pintype "passive"))
      (node (ref "L5") (pin "2") (pinfunction "2_2") (pintype "passive"))
      (node (ref "L6") (pin "2") (pinfunction "2_2") (pintype "passive"))
      (node (ref "L7") (pin "2") (pinfunction "2_2") (pintype "passive"))
      (node (ref "L800") (pin "2") (pinfunction "2_2") (pintype "passive"))
      (node (ref "L820") (pin "2") (pinfunction "2_2") (pintype "passive"))
      (node (ref "U024") (pin "20") (pinfunction "VCC_20") (pintype "power_in"))
    )
    (net (code "2") (name "+12V") (class "Default")
      (node (ref "C041") (pin "1") (pinfunction "1_1") (pintype "passive"))
      (node (ref "C043") (pin "1") (pinfunction "1_1") (pintype "passive"))
      (node (ref "C045") (pin "1") (pinfunction "1_1") (pintype "passive"))
      (node (ref "C047") (pin "1") (pinfunction "1_1") (pintype "passive"))
      (node (ref "C049") (pin "1") (pinfunction "1_1") (pintype "passive"))
      (node (ref "C051") (pin "1") (pinfunction "1_1") (pintype "passive"))
      (node (ref "C053") (pin "1") (pinfunction "1_1") (pintype "passive"))
      (node (ref "C055") (pin "1") (pinfunction "1_1") (pintype "passive"))
      (node (ref "C057") (pin "1") (pinfunction "1_1") (pintype "passive"))
      (node (ref "IC1") (pin "1") (pinfunction "VI_1") (pintype "input"))
      (node (ref "IC2") (pin "1") (pinfunction "VI_1") (pintype "input"))
      (node (ref "IC3") (pin "1") (pinfunction "VI_1") (pintype "input"))
      (node (ref "IC4") (pin "1") (pinfunction "VI_1") (pintype "input"))
      (node (ref "IC5") (pin "1") (pinfunction "VI_1") (pintype "input"))
      (node (ref "IC6") (pin "1") (pinfunction "VI_1") (pintype "input"))
      (node (ref "IC7") (pin "1") (pinfunction "VI_1") (pintype "input"))
      (node (ref "IC8") (pin "1") (pinfunction "VI_1") (pintype "input"))
      (node (ref "IC9") (pin "1") (pinfunction "VI_1") (pintype "input"))
      (node (ref "X003") (pin "2") (pinfunction "P_2") (pintype "passive"))
    )
    (net (code "3") (name "/BOARD_0Y") (class "Default")
      (node (ref "U025") (pin "8") (pinfunction "OUTA1_8") (pintype "bidirectional"))
      (node (ref "X000") (pin "1") (pinfunction "1_1") (pintype "passive"))
    )
    (net (code "4") (name "/BOARD_0Z") (class "Default")
      (node (ref "U025") (pin "7") (pinfunction "OUTA2_7") (pintype "bidirectional"))
      (node (ref "X000") (pin "2") (pinfunction "2_2") (pintype "passive"))
    )
    (net (code "5") (name "/BOARD_0_F") (class "Default")
      (node (ref "IC10") (pin "1") (pinfunction "A0_1") (pintype "input"))
      (node (ref "IC11") (pin "11") (pinfunction "A_11") (pintype "input"))
      (node (ref "IC12") (pin "11") (pinfunction "A_11") (pintype "input"))
      (node (ref "U008") (pin "1") (pinfunction "DO_1") (pintype "passive"))
    )
    (net (code "6") (name "/BOARD_1Y") (class "Default")
      (node (ref "U001") (pin "8") (pinfunction "OUTA1_8") (pintype "bidirectional"))
      (node (ref "X004") (pin "1") (pinfunction "1_1") (pintype "passive"))
    )
    (net (code "7") (name "/BOARD_1Z") (class "Default")
      (node (ref "U001") (pin "7") (pinfunction "OUTA2_7") (pintype "bidirectional"))
      (node (ref "X004") (pin "2") (pinfunction "2_2") (pintype "passive"))
    )
    (net (code "8") (name "/BOARD_1_F") (class "Default")
      (node (ref "IC10") (pin "2") (pinfunction "A1_2") (pintype "input"))
      (node (ref "IC11") (pin "10") (pinfunction "B_10") (pintype "input"))
      (node (ref "IC12") (pin "10") (pinfunction "B_10") (pintype "input"))
      (node (ref "U006") (pin "1") (pinfunction "DO_1") (pintype "passive"))
    )
    (net (code "9") (name "/BOARD_2Y") (class "Default")
      (node (ref "U030") (pin "8") (pinfunction "OUTA1_8") (pintype "bidirectional"))
      (node (ref "X007") (pin "1") (pinfunction "1_1") (pintype "passive"))
    )
    (net (code "10") (name "/BOARD_2Z") (class "Default")
      (node (ref "U030") (pin "7") (pinfunction "OUTA2_7") (pintype "bidirectional"))
      (node (ref "X007") (pin "2") (pinfunction "2_2") (pintype "passive"))
    )
    (net (code "11") (name "/BOARD_2_F") (class "Default")
      (node (ref "IC10") (pin "3") (pinfunction "A2_3") (pintype "input"))
      (node (ref "IC11") (pin "9") (pinfunction "C_9") (pintype "input"))
      (node (ref "IC12") (pin "9") (pinfunction "C_9") (pintype "input"))
      (node (ref "U005") (pin "1") (pinfunction "DO_1") (pintype "passive"))
    )
    (net (code "12") (name "/BOARD_3Y") (class "Default")
      (node (ref "U011") (pin "8") (pinfunction "OUTA1_8") (pintype "bidirectional"))
      (node (ref "X010") (pin "1") (pinfunction "1_1") (pintype "passive"))
    )
    (net (code "13") (name "/BOARD_3Z") (class "Default")
      (node (ref "U011") (pin "7") (pinfunction "OUTA2_7") (pintype "bidirectional"))
      (node (ref "X010") (pin "2") (pinfunction "2_2") (pintype "passive"))
    )
    (net (code "14") (name "/BOARD_4Y") (class "Default")
      (node (ref "U015") (pin "8") (pinfunction "OUTA1_8") (pintype "bidirectional"))
      (node (ref "X013") (pin "1") (pinfunction "1_1") (pintype "passive"))
    )
    (net (code "15") (name "/BOARD_4Z") (class "Default")
      (node (ref "U015") (pin "7") (pinfunction "OUTA2_7") (pintype "bidirectional"))
      (node (ref "X013") (pin "2") (pinfunction "2_2") (pintype "passive"))
    )
    (net (code "16") (name "/BOARD_5Y") (class "Default")
      (node (ref "U017") (pin "8") (pinfunction "OUTA1_8") (pintype "bidirectional"))
      (node (ref "X016") (pin "1") (pinfunction "1_1") (pintype "passive"))
    )
    (net (code "17") (name "/BOARD_5Z") (class "Default")
      (node (ref "U017") (pin "7") (pinfunction "OUTA2_7") (pintype "bidirectional"))
      (node (ref "X016") (pin "2") (pinfunction "2_2") (pintype "passive"))
    )
    (net (code "18") (name "/BOARD_6Y") (class "Default")
      (node (ref "U019") (pin "8") (pinfunction "OUTA1_8") (pintype "bidirectional"))
      (node (ref "X019") (pin "1") (pinfunction "1_1") (pintype "passive"))
    )
    (net (code "19") (name "/BOARD_6Z") (class "Default")
      (node (ref "U019") (pin "7") (pinfunction "OUTA2_7") (pintype "bidirectional"))
      (node (ref "X019") (pin "2") (pinfunction "2_2") (pintype "passive"))
    )
    (net (code "20") (name "/BOARD_7Y") (class "Default")
      (node (ref "U021") (pin "8") (pinfunction "OUTA1_8") (pintype "bidirectional"))
      (node (ref "X022") (pin "1") (pinfunction "1_1") (pintype "passive"))
    )
    (net (code "21") (name "/BOARD_7Z") (class "Default")
      (node (ref "U021") (pin "7") (pinfunction "OUTA2_7") (pintype "bidirectional"))
      (node (ref "X022") (pin "2") (pinfunction "2_2") (pintype "passive"))
    )
    (net (code "22") (name "/FUNCTION_0") (class "Default")
      (node (ref "U009") (pin "2") (pinfunction "INA_2") (pintype "bidirectional"))
      (node (ref "U012") (pin "2") (pinfunction "INA_2") (pintype "bidirectional"))
      (node (ref "U016") (pin "2") (pinfunction "INA_2") (pintype "bidirectional"))
      (node (ref "U018") (pin "2") (pinfunction "INA_2") (pintype "bidirectional"))
      (node (ref "U020") (pin "2") (pinfunction "INA_2") (pintype "bidirectional"))
      (node (ref "U022") (pin "2") (pinfunction "INA_2") (pintype "bidirectional"))
      (node (ref "U024") (pin "14") (pinfunction "Y3_14") (pintype "tri_state"))
      (node (ref "U026") (pin "2") (pinfunction "INA_2") (pintype "bidirectional"))
      (node (ref "U031") (pin "2") (pinfunction "INA_2") (pintype "bidirectional"))
    )
    (net (code "23") (name "/FUNCTION_0_0Y") (class "Default")
      (node (ref "U026") (pin "8") (pinfunction "OUTA1_8") (pintype "bidirectional"))
      (node (ref "X000") (pin "4") (pinfunction "4_4") (pintype "passive"))
    )
    (net (code "24") (name "/FUNCTION_0_0Z") (class "Default")
      (node (ref "U026") (pin "7") (pinfunction "OUTA2_7") (pintype "bidirectional"))
      (node (ref "X000") (pin "5") (pinfunction "5_5") (pintype "passive"))
    )
    (net (code "25") (name "/FUNCTION_0_1Y") (class "Default")
      (node (ref "U009") (pin "8") (pinfunction "OUTA1_8") (pintype "bidirectional"))
      (node (ref "X004") (pin "4") (pinfunction "4_4") (pintype "passive"))
    )
    (net (code "26") (name "/FUNCTION_0_1Z") (class "Default")
      (node (ref "U009") (pin "7") (pinfunction "OUTA2_7") (pintype "bidirectional"))
      (node (ref "X004") (pin "5") (pinfunction "5_5") (pintype "passive"))
    )
    (net (code "27") (name "/FUNCTION_0_2Y") (class "Default")
      (node (ref "U031") (pin "8") (pinfunction "OUTA1_8") (pintype "bidirectional"))
      (node (ref "X007") (pin "4") (pinfunction "4_4") (pintype "passive"))
    )
    (net (code "28") (name "/FUNCTION_0_2Z") (class "Default")
      (node (ref "U031") (pin "7") (pinfunction "OUTA2_7") (pintype "bidirectional"))
      (node (ref "X007") (pin "5") (pinfunction "5_5") (pintype "passive"))
    )
    (net (code "29") (name "/FUNCTION_0_3Y") (class "Default")
      (node (ref "U012") (pin "8") (pinfunction "OUTA1_8") (pintype "bidirectional"))
      (node (ref "X010") (pin "4") (pinfunction "4_4") (pintype "passive"))
    )
    (net (code "30") (name "/FUNCTION_0_3Z") (class "Default")
      (node (ref "U012") (pin "7") (pinfunction "OUTA2_7") (pintype "bidirectional"))
      (node (ref "X010") (pin "5") (pinfunction "5_5") (pintype "passive"))
    )
    (net (code "31") (name "/FUNCTION_0_4Y") (class "Default")
      (node (ref "U016") (pin "8") (pinfunction "OUTA1_8") (pintype "bidirectional"))
      (node (ref "X013") (pin "4") (pinfunction "4_4") (pintype "passive"))
    )
    (net (code "32") (name "/FUNCTION_0_4Z") (class "Default")
      (node (ref "U016") (pin "7") (pinfunction "OUTA2_7") (pintype "bidirectional"))
      (node (ref "X013") (pin "5") (pinfunction "5_5") (pintype "passive"))
    )
    (net (code "33") (name "/FUNCTION_0_5Y") (class "Default")
      (node (ref "U018") (pin "8") (pinfunction "OUTA1_8") (pintype "bidirectional"))
      (node (ref "X016") (pin "4") (pinfunction "4_4") (pintype "passive"))
    )
    (net (code "34") (name "/FUNCTION_0_5Z") (class "Default")
      (node (ref "U018") (pin "7") (pinfunction "OUTA2_7") (pintype "bidirectional"))
      (node (ref "X016") (pin "5") (pinfunction "5_5") (pintype "passive"))
    )
    (net (code "35") (name "/FUNCTION_0_6Y") (class "Default")
      (node (ref "U020") (pin "8") (pinfunction "OUTA1_8") (pintype "bidirectional"))
      (node (ref "X019") (pin "4") (pinfunction "4_4") (pintype "passive"))
    )
    (net (code "36") (name "/FUNCTION_0_6Z") (class "Default")
      (node (ref "U020") (pin "7") (pinfunction "OUTA2_7") (pintype "bidirectional"))
      (node (ref "X019") (pin "5") (pinfunction "5_5") (pintype "passive"))
    )
    (net (code "37") (name "/FUNCTION_0_7Y") (class "Default")
      (node (ref "U022") (pin "8") (pinfunction "OUTA1_8") (pintype "bidirectional"))
      (node (ref "X022") (pin "4") (pinfunction "4_4") (pintype "passive"))
    )
    (net (code "38") (name "/FUNCTION_0_7Z") (class "Default")
      (node (ref "U022") (pin "7") (pinfunction "OUTA2_7") (pintype "bidirectional"))
      (node (ref "X022") (pin "5") (pinfunction "5_5") (pintype "passive"))
    )
    (net (code "39") (name "/FUNCTION_0_F") (class "Default")
      (node (ref "U004") (pin "1") (pinfunction "DO_1") (pintype "passive"))
      (node (ref "U024") (pin "6") (pinfunction "A3_6") (pintype "input"))
    )
    (net (code "40") (name "/FUNCTION_1") (class "Default")
      (node (ref "U009") (pin "3") (pinfunction "INB_3") (pintype "bidirectional"))
      (node (ref "U012") (pin "3") (pinfunction "INB_3") (pintype "bidirectional"))
      (node (ref "U016") (pin "3") (pinfunction "INB_3") (pintype "bidirectional"))
      (node (ref "U018") (pin "3") (pinfunction "INB_3") (pintype "bidirectional"))
      (node (ref "U020") (pin "3") (pinfunction "INB_3") (pintype "bidirectional"))
      (node (ref "U022") (pin "3") (pinfunction "INB_3") (pintype "bidirectional"))
      (node (ref "U024") (pin "12") (pinfunction "Y4_12") (pintype "tri_state"))
      (node (ref "U026") (pin "3") (pinfunction "INB_3") (pintype "bidirectional"))
      (node (ref "U031") (pin "3") (pinfunction "INB_3") (pintype "bidirectional"))
    )
    (net (code "41") (name "/FUNCTION_1_0Y") (class "Default")
      (node (ref "U026") (pin "6") (pinfunction "OUTB1_6") (pintype "bidirectional"))
      (node (ref "X000") (pin "6") (pinfunction "6_6") (pintype "passive"))
    )
    (net (code "42") (name "/FUNCTION_1_0Z") (class "Default")
      (node (ref "U026") (pin "5") (pinfunction "OUTB2_5") (pintype "bidirectional"))
      (node (ref "X000") (pin "3") (pinfunction "3_3") (pintype "passive"))
    )
    (net (code "43") (name "/FUNCTION_1_1Y") (class "Default")
      (node (ref "U009") (pin "6") (pinfunction "OUTB1_6") (pintype "bidirectional"))
      (node (ref "X004") (pin "6") (pinfunction "6_6") (pintype "passive"))
    )
    (net (code "44") (name "/FUNCTION_1_1Z") (class "Default")
      (node (ref "U009") (pin "5") (pinfunction "OUTB2_5") (pintype "bidirectional"))
      (node (ref "X004") (pin "3") (pinfunction "3_3") (pintype "passive"))
    )
    (net (code "45") (name "/FUNCTION_1_2Y") (class "Default")
      (node (ref "U031") (pin "6") (pinfunction "OUTB1_6") (pintype "bidirectional"))
      (node (ref "X007") (pin "6") (pinfunction "6_6") (pintype "passive"))
    )
    (net (code "46") (name "/FUNCTION_1_2Z") (class "Default")
      (node (ref "U031") (pin "5") (pinfunction "OUTB2_5") (pintype "bidirectional"))
      (node (ref "X007") (pin "3") (pinfunction "3_3") (pintype "passive"))
    )
    (net (code "47") (name "/FUNCTION_1_3Y") (class "Default")
      (node (ref "U012") (pin "6") (pinfunction "OUTB1_6") (pintype "bidirectional"))
      (node (ref "X010") (pin "6") (pinfunction "6_6") (pintype "passive"))
    )
    (net (code "48") (name "/FUNCTION_1_3Z") (class "Default")
      (node (ref "U012") (pin "5") (pinfunction "OUTB2_5") (pintype "bidirectional"))
      (node (ref "X010") (pin "3") (pinfunction "3_3") (pintype "passive"))
    )
    (net (code "49") (name "/FUNCTION_1_4Y") (class "Default")
      (node (ref "U016") (pin "6") (pinfunction "OUTB1_6") (pintype "bidirectional"))
      (node (ref "X013") (pin "6") (pinfunction "6_6") (pintype "passive"))
    )
    (net (code "50") (name "/FUNCTION_1_4Z") (class "Default")
      (node (ref "U016") (pin "5") (pinfunction "OUTB2_5") (pintype "bidirectional"))
      (node (ref "X013") (pin "3") (pinfunction "3_3") (pintype "passive"))
    )
    (net (code "51") (name "/FUNCTION_1_5Y") (class "Default")
      (node (ref "U018") (pin "6") (pinfunction "OUTB1_6") (pintype "bidirectional"))
      (node (ref "X016") (pin "6") (pinfunction "6_6") (pintype "passive"))
    )
    (net (code "52") (name "/FUNCTION_1_5Z") (class "Default")
      (node (ref "U018") (pin "5") (pinfunction "OUTB2_5") (pintype "bidirectional"))
      (node (ref "X016") (pin "3") (pinfunction "3_3") (pintype "passive"))
    )
    (net (code "53") (name "/FUNCTION_1_6Y") (class "Default")
      (node (ref "U020") (pin "6") (pinfunction "OUTB1_6") (pintype "bidirectional"))
      (node (ref "X019") (pin "6") (pinfunction "6_6") (pintype "passive"))
    )
    (net (code "54") (name "/FUNCTION_1_6Z") (class "Default")
      (node (ref "U020") (pin "5") (pinfunction "OUTB2_5") (pintype "bidirectional"))
      (node (ref "X019") (pin "3") (pinfunction "3_3") (pintype "passive"))
    )
    (net (code "55") (name "/FUNCTION_1_7Y") (class "Default")
      (node (ref "U022") (pin "6") (pinfunction "OUTB1_6") (pintype "bidirectional"))
      (node (ref "X022") (pin "6") (pinfunction "6_6") (pintype "passive"))
    )
    (net (code "56") (name "/FUNCTION_1_7Z") (class "Default")
      (node (ref "U022") (pin "5") (pinfunction "OUTB2_5") (pintype "bidirectional"))
      (node (ref "X022") (pin "3") (pinfunction "3_3") (pintype "passive"))
    )
    (net (code "57") (name "/FUNCTION_1_F") (class "Default")
      (node (ref "U007") (pin "1") (pinfunction "DO_1") (pintype "passive"))
      (node (ref "U024") (pin "8") (pinfunction "A4_8") (pintype "input"))
    )
    (net (code "58") (name "/MISO") (class "Default")
      (node (ref "IC12") (pin "5") (pinfunction "Y_5") (pintype "output"))
      (node (ref "R800") (pin "2") (pinfunction "2_2") (pintype "passive"))
      (node (ref "U800") (pin "4") (pinfunction "DIN_4") (pintype "bidirectional"))
    )
    (net (code "59") (name "/MISO_0") (class "Default")
      (node (ref "IC12") (pin "13") (pinfunction "D6_13") (pintype "input"))
      (node (ref "U028") (pin "3") (pinfunction "OUTB_3") (pintype "bidirectional"))
    )
    (net (code "60") (name "/MISO_1") (class "Default")
      (node (ref "IC12") (pin "14") (pinfunction "D5_14") (pintype "input"))
      (node (ref "U029") (pin "3") (pinfunction "OUTB_3") (pintype "bidirectional"))
    )
    (net (code "61") (name "/MISO_2") (class "Default")
      (node (ref "IC12") (pin "15") (pinfunction "D4_15") (pintype "input"))
      (node (ref "U033") (pin "3") (pinfunction "OUTB_3") (pintype "bidirectional"))
    )
    (net (code "62") (name "/MISO_3") (class "Default")
      (node (ref "IC12") (pin "1") (pinfunction "D3_1") (pintype "input"))
      (node (ref "U014") (pin "3") (pinfunction "OUTB_3") (pintype "bidirectional"))
    )
    (net (code "63") (name "/MISO_4") (class "Default")
      (node (ref "IC12") (pin "2") (pinfunction "D2_2") (pintype "input"))
      (node (ref "U035") (pin "3") (pinfunction "OUTB_3") (pintype "bidirectional"))
    )
    (net (code "64") (name "/MISO_5") (class "Default")
      (node (ref "IC12") (pin "3") (pinfunction "D1_3") (pintype "input"))
      (node (ref "U037") (pin "3") (pinfunction "INB_3") (pintype "bidirectional"))
    )
    (net (code "65") (name "/MISO_6") (class "Default")
      (node (ref "IC12") (pin "4") (pinfunction "D0_4") (pintype "input"))
      (node (ref "U039") (pin "3") (pinfunction "OUTB_3") (pintype "bidirectional"))
    )
    (net (code "66") (name "/MISO_7") (class "Default")
      (node (ref "IC12") (pin "12") (pinfunction "D7_12") (pintype "input"))
      (node (ref "U041") (pin "3") (pinfunction "OUTB_3") (pintype "bidirectional"))
    )
    (net (code "67") (name "/MISO_A_0") (class "Default")
      (node (ref "R000") (pin "2") (pinfunction "2_2") (pintype "passive"))
      (node (ref "U028") (pin "6") (pinfunction "INB1_6") (pintype "bidirectional"))
      (node (ref "X001") (pin "2") (pinfunction "2_2") (pintype "passive"))
    )
    (net (code "68") (name "/MISO_A_1") (class "Default")
      (node (ref "R003") (pin "2") (pinfunction "2_2") (pintype "passive"))
      (node (ref "U029") (pin "6") (pinfunction "INB1_6") (pintype "bidirectional"))
      (node (ref "X005") (pin "2") (pinfunction "2_2") (pintype "passive"))
    )
    (net (code "69") (name "/MISO_A_2") (class "Default")
      (node (ref "R005") (pin "2") (pinfunction "2_2") (pintype "passive"))
      (node (ref "U033") (pin "6") (pinfunction "INB1_6") (pintype "bidirectional"))
      (node (ref "X008") (pin "2") (pinfunction "2_2") (pintype "passive"))
    )
    (net (code "70") (name "/MISO_A_3") (class "Default")
      (node (ref "R007") (pin "2") (pinfunction "2_2") (pintype "passive"))
      (node (ref "U014") (pin "6") (pinfunction "INB1_6") (pintype "bidirectional"))
      (node (ref "X011") (pin "2") (pinfunction "2_2") (pintype "passive"))
    )
    (net (code "71") (name "/MISO_A_4") (class "Default")
      (node (ref "R009") (pin "2") (pinfunction "2_2") (pintype "passive"))
      (node (ref "U035") (pin "6") (pinfunction "INB1_6") (pintype "bidirectional"))
      (node (ref "X014") (pin "2") (pinfunction "2_2") (pintype "passive"))
    )
    (net (code "72") (name "/MISO_A_5") (class "Default")
      (node (ref "R011") (pin "2") (pinfunction "2_2") (pintype "passive"))
      (node (ref "U037") (pin "6") (pinfunction "OUTB1_6") (pintype "bidirectional"))
      (node (ref "X017") (pin "2") (pinfunction "2_2") (pintype "passive"))
    )
    (net (code "73") (name "/MISO_A_6") (class "Default")
      (node (ref "R013") (pin "2") (pinfunction "2_2") (pintype "passive"))
      (node (ref "U039") (pin "6") (pinfunction "INB1_6") (pintype "bidirectional"))
      (node (ref "X020") (pin "2") (pinfunction "2_2") (pintype "passive"))
    )
    (net (code "74") (name "/MISO_A_7") (class "Default")
      (node (ref "R015") (pin "2") (pinfunction "2_2") (pintype "passive"))
      (node (ref "U041") (pin "6") (pinfunction "INB1_6") (pintype "bidirectional"))
      (node (ref "X023") (pin "2") (pinfunction "2_2") (pintype "passive"))
    )
    (net (code "75") (name "/MISO_B_0") (class "Default")
      (node (ref "R000") (pin "1") (pinfunction "1_1") (pintype "passive"))
      (node (ref "U028") (pin "5") (pinfunction "INB2_5") (pintype "bidirectional"))
      (node (ref "X001") (pin "1") (pinfunction "1_1") (pintype "passive"))
    )
    (net (code "76") (name "/MISO_B_1") (class "Default")
      (node (ref "R003") (pin "1") (pinfunction "1_1") (pintype "passive"))
      (node (ref "U029") (pin "5") (pinfunction "INB2_5") (pintype "bidirectional"))
      (node (ref "X005") (pin "1") (pinfunction "1_1") (pintype "passive"))
    )
    (net (code "77") (name "/MISO_B_2") (class "Default")
      (node (ref "R005") (pin "1") (pinfunction "1_1") (pintype "passive"))
      (node (ref "U033") (pin "5") (pinfunction "INB2_5") (pintype "bidirectional"))
      (node (ref "X008") (pin "1") (pinfunction "1_1") (pintype "passive"))
    )
    (net (code "78") (name "/MISO_B_3") (class "Default")
      (node (ref "R007") (pin "1") (pinfunction "1_1") (pintype "passive"))
      (node (ref "U014") (pin "5") (pinfunction "INB2_5") (pintype "bidirectional"))
      (node (ref "X011") (pin "1") (pinfunction "1_1") (pintype "passive"))
    )
    (net (code "79") (name "/MISO_B_4") (class "Default")
      (node (ref "R009") (pin "1") (pinfunction "1_1") (pintype "passive"))
      (node (ref "U035") (pin "5") (pinfunction "INB2_5") (pintype "bidirectional"))
      (node (ref "X014") (pin "1") (pinfunction "1_1") (pintype "passive"))
    )
    (net (code "80") (name "/MISO_B_5") (class "Default")
      (node (ref "R011") (pin "1") (pinfunction "1_1") (pintype "passive"))
      (node (ref "U037") (pin "5") (pinfunction "OUTB2_5") (pintype "bidirectional"))
      (node (ref "X017") (pin "1") (pinfunction "1_1") (pintype "passive"))
    )
    (net (code "81") (name "/MISO_B_6") (class "Default")
      (node (ref "R013") (pin "1") (pinfunction "1_1") (pintype "passive"))
      (node (ref "U039") (pin "5") (pinfunction "INB2_5") (pintype "bidirectional"))
      (node (ref "X020") (pin "1") (pinfunction "1_1") (pintype "passive"))
    )
    (net (code "82") (name "/MISO_B_7") (class "Default")
      (node (ref "R015") (pin "1") (pinfunction "1_1") (pintype "passive"))
      (node (ref "U041") (pin "5") (pinfunction "INB2_5") (pintype "bidirectional"))
      (node (ref "X023") (pin "1") (pinfunction "1_1") (pintype "passive"))
    )
    (net (code "83") (name "/MOSI") (class "Default")
      (node (ref "U010") (pin "2") (pinfunction "INA_2") (pintype "bidirectional"))
      (node (ref "U013") (pin "2") (pinfunction "INA_2") (pintype "bidirectional"))
      (node (ref "U024") (pin "18") (pinfunction "Y1_18") (pintype "tri_state"))
      (node (ref "U027") (pin "2") (pinfunction "INA_2") (pintype "bidirectional"))
      (node (ref "U032") (pin "2") (pinfunction "INA_2") (pintype "bidirectional"))
      (node (ref "U034") (pin "2") (pinfunction "INA_2") (pintype "bidirectional"))
      (node (ref "U036") (pin "2") (pinfunction "INA_2") (pintype "bidirectional"))
      (node (ref "U038") (pin "2") (pinfunction "INA_2") (pintype "bidirectional"))
      (node (ref "U040") (pin "2") (pinfunction "INA_2") (pintype "bidirectional"))
    )
    (net (code "84") (name "/MOSI_A_0") (class "Default")
      (node (ref "U027") (pin "8") (pinfunction "OUTA1_8") (pintype "bidirectional"))
      (node (ref "X001") (pin "8") (pinfunction "8_8") (pintype "passive"))
    )
    (net (code "85") (name "/MOSI_A_1") (class "Default")
      (node (ref "U010") (pin "8") (pinfunction "OUTA1_8") (pintype "bidirectional"))
      (node (ref "X005") (pin "8") (pinfunction "8_8") (pintype "passive"))
    )
    (net (code "86") (name "/MOSI_A_2") (class "Default")
      (node (ref "U032") (pin "8") (pinfunction "OUTA1_8") (pintype "bidirectional"))
      (node (ref "X008") (pin "8") (pinfunction "8_8") (pintype "passive"))
    )
    (net (code "87") (name "/MOSI_A_3") (class "Default")
      (node (ref "U013") (pin "8") (pinfunction "OUTA1_8") (pintype "bidirectional"))
      (node (ref "X011") (pin "8") (pinfunction "8_8") (pintype "passive"))
    )
    (net (code "88") (name "/MOSI_A_4") (class "Default")
      (node (ref "U034") (pin "8") (pinfunction "OUTA1_8") (pintype "bidirectional"))
      (node (ref "X014") (pin "8") (pinfunction "8_8") (pintype "passive"))
    )
    (net (code "89") (name "/MOSI_A_5") (class "Default")
      (node (ref "U036") (pin "8") (pinfunction "OUTA1_8") (pintype "bidirectional"))
      (node (ref "X017") (pin "8") (pinfunction "8_8") (pintype "passive"))
    )
    (net (code "90") (name "/MOSI_A_6") (class "Default")
      (node (ref "U038") (pin "8") (pinfunction "OUTA1_8") (pintype "bidirectional"))
      (node (ref "X020") (pin "8") (pinfunction "8_8") (pintype "passive"))
    )
    (net (code "91") (name "/MOSI_A_7") (class "Default")
      (node (ref "U040") (pin "8") (pinfunction "OUTA1_8") (pintype "bidirectional"))
      (node (ref "X023") (pin "8") (pinfunction "8_8") (pintype "passive"))
    )
    (net (code "92") (name "/MOSI_B_0") (class "Default")
      (node (ref "U027") (pin "7") (pinfunction "OUTA2_7") (pintype "bidirectional"))
      (node (ref "X001") (pin "7") (pinfunction "7_7") (pintype "passive"))
    )
    (net (code "93") (name "/MOSI_B_1") (class "Default")
      (node (ref "U010") (pin "7") (pinfunction "OUTA2_7") (pintype "bidirectional"))
      (node (ref "X005") (pin "7") (pinfunction "7_7") (pintype "passive"))
    )
    (net (code "94") (name "/MOSI_B_2") (class "Default")
      (node (ref "U032") (pin "7") (pinfunction "OUTA2_7") (pintype "bidirectional"))
      (node (ref "X008") (pin "7") (pinfunction "7_7") (pintype "passive"))
    )
    (net (code "95") (name "/MOSI_B_3") (class "Default")
      (node (ref "U013") (pin "7") (pinfunction "OUTA2_7") (pintype "bidirectional"))
      (node (ref "X011") (pin "7") (pinfunction "7_7") (pintype "passive"))
    )
    (net (code "96") (name "/MOSI_B_4") (class "Default")
      (node (ref "U034") (pin "7") (pinfunction "OUTA2_7") (pintype "bidirectional"))
      (node (ref "X014") (pin "7") (pinfunction "7_7") (pintype "passive"))
    )
    (net (code "97") (name "/MOSI_B_5") (class "Default")
      (node (ref "U036") (pin "7") (pinfunction "OUTA2_7") (pintype "bidirectional"))
      (node (ref "X017") (pin "7") (pinfunction "7_7") (pintype "passive"))
    )
    (net (code "98") (name "/MOSI_B_6") (class "Default")
      (node (ref "U038") (pin "7") (pinfunction "OUTA2_7") (pintype "bidirectional"))
      (node (ref "X020") (pin "7") (pinfunction "7_7") (pintype "passive"))
    )
    (net (code "99") (name "/MOSI_B_7") (class "Default")
      (node (ref "U040") (pin "7") (pinfunction "OUTA2_7") (pintype "bidirectional"))
      (node (ref "X023") (pin "7") (pinfunction "7_7") (pintype "passive"))
    )
    (net (code "100") (name "/MOSI_F") (class "Default")
      (node (ref "U003") (pin "1") (pinfunction "DO_1") (pintype "passive"))
      (node (ref "U024") (pin "2") (pinfunction "A1_2") (pintype "input"))
    )
    (net (code "101") (name "/RE_0") (class "Default")
      (node (ref "IC10") (pin "9") (pinfunction "Y6_9") (pintype "output"))
      (node (ref "U025") (pin "2") (pinfunction "INA_2") (pintype "bidirectional"))
    )
    (net (code "102") (name "/RE_1") (class "Default")
      (node (ref "IC10") (pin "10") (pinfunction "Y5_10") (pintype "output"))
      (node (ref "U001") (pin "2") (pinfunction "INA_2") (pintype "bidirectional"))
    )
    (net (code "103") (name "/RE_2") (class "Default")
      (node (ref "IC10") (pin "11") (pinfunction "Y4_11") (pintype "output"))
      (node (ref "U030") (pin "2") (pinfunction "INA_2") (pintype "bidirectional"))
    )
    (net (code "104") (name "/RE_3") (class "Default")
      (node (ref "IC10") (pin "12") (pinfunction "Y3_12") (pintype "output"))
      (node (ref "U011") (pin "2") (pinfunction "INA_2") (pintype "bidirectional"))
    )
    (net (code "105") (name "/RE_4") (class "Default")
      (node (ref "IC10") (pin "13") (pinfunction "Y2_13") (pintype "output"))
      (node (ref "U015") (pin "2") (pinfunction "INA_2") (pintype "bidirectional"))
    )
    (net (code "106") (name "/RE_5") (class "Default")
      (node (ref "IC10") (pin "14") (pinfunction "Y1_14") (pintype "output"))
      (node (ref "U017") (pin "2") (pinfunction "INA_2") (pintype "bidirectional"))
    )
    (net (code "107") (name "/RE_6") (class "Default")
      (node (ref "IC10") (pin "15") (pinfunction "Y0_15") (pintype "output"))
      (node (ref "U019") (pin "2") (pinfunction "INA_2") (pintype "bidirectional"))
    )
    (net (code "108") (name "/RE_7") (class "Default")
      (node (ref "IC10") (pin "7") (pinfunction "Y7_7") (pintype "output"))
      (node (ref "U021") (pin "2") (pinfunction "INA_2") (pintype "bidirectional"))
    )
    (net (code "109") (name "/SCKI") (class "Default")
      (node (ref "IC11") (pin "5") (pinfunction "Y_5") (pintype "output"))
      (node (ref "R002") (pin "2") (pinfunction "2_2") (pintype "passive"))
      (node (ref "U002") (pin "4") (pinfunction "DIN_4") (pintype "bidirectional"))
    )
    (net (code "110") (name "/SCKO_F") (class "Default")
      (node (ref "U024") (pin "4") (pinfunction "A2_4") (pintype "input"))
      (node (ref "U820") (pin "1") (pinfunction "DO_1") (pintype "passive"))
    )
    (net (code "111") (name "/SCK_MS") (class "Default")
      (node (ref "U010") (pin "3") (pinfunction "INB_3") (pintype "bidirectional"))
      (node (ref "U013") (pin "3") (pinfunction "INB_3") (pintype "bidirectional"))
      (node (ref "U024") (pin "16") (pinfunction "Y2_16") (pintype "tri_state"))
      (node (ref "U027") (pin "3") (pinfunction "INB_3") (pintype "bidirectional"))
      (node (ref "U032") (pin "3") (pinfunction "INB_3") (pintype "bidirectional"))
      (node (ref "U034") (pin "3") (pinfunction "INB_3") (pintype "bidirectional"))
      (node (ref "U036") (pin "3") (pinfunction "INB_3") (pintype "bidirectional"))
      (node (ref "U038") (pin "3") (pinfunction "INB_3") (pintype "bidirectional"))
      (node (ref "U040") (pin "3") (pinfunction "INB_3") (pintype "bidirectional"))
    )
    (net (code "112") (name "/SCK_MS_A_0") (class "Default")
      (node (ref "U027") (pin "6") (pinfunction "OUTB1_6") (pintype "bidirectional"))
      (node (ref "X001") (pin "5") (pinfunction "5_5") (pintype "passive"))
    )
    (net (code "113") (name "/SCK_MS_A_1") (class "Default")
      (node (ref "U010") (pin "6") (pinfunction "OUTB1_6") (pintype "bidirectional"))
      (node (ref "X005") (pin "5") (pinfunction "5_5") (pintype "passive"))
    )
    (net (code "114") (name "/SCK_MS_A_2") (class "Default")
      (node (ref "U032") (pin "6") (pinfunction "OUTB1_6") (pintype "bidirectional"))
      (node (ref "X008") (pin "5") (pinfunction "5_5") (pintype "passive"))
    )
    (net (code "115") (name "/SCK_MS_A_3") (class "Default")
      (node (ref "U013") (pin "6") (pinfunction "OUTB1_6") (pintype "bidirectional"))
      (node (ref "X011") (pin "5") (pinfunction "5_5") (pintype "passive"))
    )
    (net (code "116") (name "/SCK_MS_A_4") (class "Default")
      (node (ref "U034") (pin "6") (pinfunction "OUTB1_6") (pintype "bidirectional"))
      (node (ref "X014") (pin "5") (pinfunction "5_5") (pintype "passive"))
    )
    (net (code "117") (name "/SCK_MS_A_5") (class "Default")
      (node (ref "U036") (pin "6") (pinfunction "OUTB1_6") (pintype "bidirectional"))
      (node (ref "X017") (pin "5") (pinfunction "5_5") (pintype "passive"))
    )
    (net (code "118") (name "/SCK_MS_A_6") (class "Default")
      (node (ref "U038") (pin "6") (pinfunction "OUTB1_6") (pintype "bidirectional"))
      (node (ref "X020") (pin "5") (pinfunction "5_5") (pintype "passive"))
    )
    (net (code "119") (name "/SCK_MS_A_7") (class "Default")
      (node (ref "U040") (pin "6") (pinfunction "OUTB1_6") (pintype "bidirectional"))
      (node (ref "X023") (pin "5") (pinfunction "5_5") (pintype "passive"))
    )
    (net (code "120") (name "/SCK_MS_B_0") (class "Default")
      (node (ref "U027") (pin "5") (pinfunction "OUTB2_5") (pintype "bidirectional"))
      (node (ref "X001") (pin "4") (pinfunction "4_4") (pintype "passive"))
    )
    (net (code "121") (name "/SCK_MS_B_1") (class "Default")
      (node (ref "U010") (pin "5") (pinfunction "OUTB2_5") (pintype "bidirectional"))
      (node (ref "X005") (pin "4") (pinfunction "4_4") (pintype "passive"))
    )
    (net (code "122") (name "/SCK_MS_B_2") (class "Default")
      (node (ref "U032") (pin "5") (pinfunction "OUTB2_5") (pintype "bidirectional"))
      (node (ref "X008") (pin "4") (pinfunction "4_4") (pintype "passive"))
    )
    (net (code "123") (name "/SCK_MS_B_3") (class "Default")
      (node (ref "U013") (pin "5") (pinfunction "OUTB2_5") (pintype "bidirectional"))
      (node (ref "X011") (pin "4") (pinfunction "4_4") (pintype "passive"))
    )
    (net (code "124") (name "/SCK_MS_B_4") (class "Default")
      (node (ref "U034") (pin "5") (pinfunction "OUTB2_5") (pintype "bidirectional"))
      (node (ref "X014") (pin "4") (pinfunction "4_4") (pintype "passive"))
    )
    (net (code "125") (name "/SCK_MS_B_5") (class "Default")
      (node (ref "U036") (pin "5") (pinfunction "OUTB2_5") (pintype "bidirectional"))
      (node (ref "X017") (pin "4") (pinfunction "4_4") (pintype "passive"))
    )
    (net (code "126") (name "/SCK_MS_B_6") (class "Default")
      (node (ref "U038") (pin "5") (pinfunction "OUTB2_5") (pintype "bidirectional"))
      (node (ref "X020") (pin "4") (pinfunction "4_4") (pintype "passive"))
    )
    (net (code "127") (name "/SCK_MS_B_7") (class "Default")
      (node (ref "U040") (pin "5") (pinfunction "OUTB2_5") (pintype "bidirectional"))
      (node (ref "X023") (pin "4") (pinfunction "4_4") (pintype "passive"))
    )
    (net (code "128") (name "/SCK_SM_0") (class "Default")
      (node (ref "IC11") (pin "13") (pinfunction "D6_13") (pintype "input"))
      (node (ref "U028") (pin "2") (pinfunction "OUTA_2") (pintype "bidirectional"))
    )
    (net (code "129") (name "/SCK_SM_1") (class "Default")
      (node (ref "IC11") (pin "14") (pinfunction "D5_14") (pintype "input"))
      (node (ref "U029") (pin "2") (pinfunction "OUTA_2") (pintype "bidirectional"))
    )
    (net (code "130") (name "/SCK_SM_2") (class "Default")
      (node (ref "IC11") (pin "15") (pinfunction "D4_15") (pintype "input"))
      (node (ref "U033") (pin "2") (pinfunction "OUTA_2") (pintype "bidirectional"))
    )
    (net (code "131") (name "/SCK_SM_3") (class "Default")
      (node (ref "IC11") (pin "1") (pinfunction "D3_1") (pintype "input"))
      (node (ref "U014") (pin "2") (pinfunction "OUTA_2") (pintype "bidirectional"))
    )
    (net (code "132") (name "/SCK_SM_4") (class "Default")
      (node (ref "IC11") (pin "2") (pinfunction "D2_2") (pintype "input"))
      (node (ref "U035") (pin "2") (pinfunction "OUTA_2") (pintype "bidirectional"))
    )
    (net (code "133") (name "/SCK_SM_5") (class "Default")
      (node (ref "IC11") (pin "3") (pinfunction "D1_3") (pintype "input"))
      (node (ref "U037") (pin "2") (pinfunction "INA_2") (pintype "bidirectional"))
    )
    (net (code "134") (name "/SCK_SM_6") (class "Default")
      (node (ref "IC11") (pin "4") (pinfunction "D0_4") (pintype "input"))
      (node (ref "U039") (pin "2") (pinfunction "OUTA_2") (pintype "bidirectional"))
    )
    (net (code "135") (name "/SCK_SM_7") (class "Default")
      (node (ref "IC11") (pin "12") (pinfunction "D7_12") (pintype "input"))
      (node (ref "U041") (pin "2") (pinfunction "OUTA_2") (pintype "bidirectional"))
    )
    (net (code "136") (name "/SCK_SM_A_0") (class "Default")
      (node (ref "R001") (pin "2") (pinfunction "2_2") (pintype "passive"))
      (node (ref "U028") (pin "8") (pinfunction "INA1_8") (pintype "bidirectional"))
      (node (ref "X001") (pin "6") (pinfunction "6_6") (pintype "passive"))
    )
    (net (code "137") (name "/SCK_SM_A_1") (class "Default")
      (node (ref "R004") (pin "2") (pinfunction "2_2") (pintype "passive"))
      (node (ref "U029") (pin "8") (pinfunction "INA1_8") (pintype "bidirectional"))
      (node (ref "X005") (pin "6") (pinfunction "6_6") (pintype "passive"))
    )
    (net (code "138") (name "/SCK_SM_A_2") (class "Default")
      (node (ref "R006") (pin "2") (pinfunction "2_2") (pintype "passive"))
      (node (ref "U033") (pin "8") (pinfunction "INA1_8") (pintype "bidirectional"))
      (node (ref "X008") (pin "6") (pinfunction "6_6") (pintype "passive"))
    )
    (net (code "139") (name "/SCK_SM_A_3") (class "Default")
      (node (ref "R008") (pin "2") (pinfunction "2_2") (pintype "passive"))
      (node (ref "U014") (pin "8") (pinfunction "INA1_8") (pintype "bidirectional"))
      (node (ref "X011") (pin "6") (pinfunction "6_6") (pintype "passive"))
    )
    (net (code "140") (name "/SCK_SM_A_4") (class "Default")
      (node (ref "R010") (pin "2") (pinfunction "2_2") (pintype "passive"))
      (node (ref "U035") (pin "8") (pinfunction "INA1_8") (pintype "bidirectional"))
      (node (ref "X014") (pin "6") (pinfunction "6_6") (pintype "passive"))
    )
    (net (code "141") (name "/SCK_SM_A_5") (class "Default")
      (node (ref "R012") (pin "2") (pinfunction "2_2") (pintype "passive"))
      (node (ref "U037") (pin "8") (pinfunction "OUTA1_8") (pintype "bidirectional"))
      (node (ref "X017") (pin "6") (pinfunction "6_6") (pintype "passive"))
    )
    (net (code "142") (name "/SCK_SM_A_6") (class "Default")
      (node (ref "R014") (pin "2") (pinfunction "2_2") (pintype "passive"))
      (node (ref "U039") (pin "8") (pinfunction "INA1_8") (pintype "bidirectional"))
      (node (ref "X020") (pin "6") (pinfunction "6_6") (pintype "passive"))
    )
    (net (code "143") (name "/SCK_SM_A_7") (class "Default")
      (node (ref "R016") (pin "2") (pinfunction "2_2") (pintype "passive"))
      (node (ref "U041") (pin "8") (pinfunction "INA1_8") (pintype "bidirectional"))
      (node (ref "X023") (pin "6") (pinfunction "6_6") (pintype "passive"))
    )
    (net (code "144") (name "/SCK_SM_B_0") (class "Default")
      (node (ref "R001") (pin "1") (pinfunction "1_1") (pintype "passive"))
      (node (ref "U028") (pin "7") (pinfunction "INA2_7") (pintype "bidirectional"))
      (node (ref "X001") (pin "3") (pinfunction "3_3") (pintype "passive"))
    )
    (net (code "145") (name "/SCK_SM_B_1") (class "Default")
      (node (ref "R004") (pin "1") (pinfunction "1_1") (pintype "passive"))
      (node (ref "U029") (pin "7") (pinfunction "INA2_7") (pintype "bidirectional"))
      (node (ref "X005") (pin "3") (pinfunction "3_3") (pintype "passive"))
    )
    (net (code "146") (name "/SCK_SM_B_2") (class "Default")
      (node (ref "R006") (pin "1") (pinfunction "1_1") (pintype "passive"))
      (node (ref "U033") (pin "7") (pinfunction "INA2_7") (pintype "bidirectional"))
      (node (ref "X008") (pin "3") (pinfunction "3_3") (pintype "passive"))
    )
    (net (code "147") (name "/SCK_SM_B_3") (class "Default")
      (node (ref "R008") (pin "1") (pinfunction "1_1") (pintype "passive"))
      (node (ref "U014") (pin "7") (pinfunction "INA2_7") (pintype "bidirectional"))
      (node (ref "X011") (pin "3") (pinfunction "3_3") (pintype "passive"))
    )
    (net (code "148") (name "/SCK_SM_B_4") (class "Default")
      (node (ref "R010") (pin "1") (pinfunction "1_1") (pintype "passive"))
      (node (ref "U035") (pin "7") (pinfunction "INA2_7") (pintype "bidirectional"))
      (node (ref "X014") (pin "3") (pinfunction "3_3") (pintype "passive"))
    )
    (net (code "149") (name "/SCK_SM_B_5") (class "Default")
      (node (ref "R012") (pin "1") (pinfunction "1_1") (pintype "passive"))
      (node (ref "U037") (pin "7") (pinfunction "OUTA2_7") (pintype "bidirectional"))
      (node (ref "X017") (pin "3") (pinfunction "3_3") (pintype "passive"))
    )
    (net (code "150") (name "/SCK_SM_B_6") (class "Default")
      (node (ref "R014") (pin "1") (pinfunction "1_1") (pintype "passive"))
      (node (ref "U039") (pin "7") (pinfunction "INA2_7") (pintype "bidirectional"))
      (node (ref "X020") (pin "3") (pinfunction "3_3") (pintype "passive"))
    )
    (net (code "151") (name "/SCK_SM_B_7") (class "Default")
      (node (ref "R016") (pin "1") (pinfunction "1_1") (pintype "passive"))
      (node (ref "U041") (pin "7") (pinfunction "INA2_7") (pintype "bidirectional"))
      (node (ref "X023") (pin "3") (pinfunction "3_3") (pintype "passive"))
    )
    (net (code "152") (name "/VDD0") (class "Default")
      (node (ref "C000") (pin "1") (pinfunction "1_1") (pintype "passive"))
      (node (ref "C001") (pin "1") (pinfunction "1_1") (pintype "passive"))
      (node (ref "C040") (pin "1") (pinfunction "1_1") (pintype "passive"))
      (node (ref "C058") (pin "1") (pinfunction "1_1") (pintype "passive"))
      (node (ref "C059") (pin "1") (pinfunction "1_1") (pintype "passive"))
      (node (ref "IC1") (pin "2") (pinfunction "VO_2") (pintype "passive"))
      (node (ref "U025") (pin "1") (pinfunction "VCC_1") (pintype "bidirectional"))
      (node (ref "U026") (pin "1") (pinfunction "VCC_1") (pintype "bidirectional"))
      (node (ref "U027") (pin "1") (pinfunction "VCC_1") (pintype "bidirectional"))
      (node (ref "U028") (pin "1") (pinfunction "VCC_1") (pintype "bidirectional"))
      (node (ref "X000") (pin "7") (pinfunction "7_7") (pintype "passive"))
    )
    (net (code "153") (name "/VDD1") (class "Default")
      (node (ref "C023") (pin "1") (pinfunction "1_1") (pintype "passive"))
      (node (ref "C024") (pin "1") (pinfunction "1_1") (pintype "passive"))
      (node (ref "C042") (pin "1") (pinfunction "1_1") (pintype "passive"))
      (node (ref "C060") (pin "1") (pinfunction "1_1") (pintype "passive"))
      (node (ref "C061") (pin "1") (pinfunction "1_1") (pintype "passive"))
      (node (ref "IC2") (pin "2") (pinfunction "VO_2") (pintype "passive"))
      (node (ref "U001") (pin "1") (pinfunction "VCC_1") (pintype "bidirectional"))
      (node (ref "U009") (pin "1") (pinfunction "VCC_1") (pintype "bidirectional"))
      (node (ref "U010") (pin "1") (pinfunction "VCC_1") (pintype "bidirectional"))
      (node (ref "U029") (pin "1") (pinfunction "VCC_1") (pintype "bidirectional"))
      (node (ref "X004") (pin "7") (pinfunction "7_7") (pintype "passive"))
    )
    (net (code "154") (name "/VDD2") (class "Default")
      (node (ref "C025") (pin "1") (pinfunction "1_1") (pintype "passive"))
      (node (ref "C026") (pin "1") (pinfunction "1_1") (pintype "passive"))
      (node (ref "C044") (pin "1") (pinfunction "1_1") (pintype "passive"))
      (node (ref "C062") (pin "1") (pinfunction "1_1") (pintype "passive"))
      (node (ref "C063") (pin "1") (pinfunction "1_1") (pintype "passive"))
      (node (ref "IC3") (pin "2") (pinfunction "VO_2") (pintype "passive"))
      (node (ref "U030") (pin "1") (pinfunction "VCC_1") (pintype "bidirectional"))
      (node (ref "U031") (pin "1") (pinfunction "VCC_1") (pintype "bidirectional"))
      (node (ref "U032") (pin "1") (pinfunction "VCC_1") (pintype "bidirectional"))
      (node (ref "U033") (pin "1") (pinfunction "VCC_1") (pintype "bidirectional"))
      (node (ref "X007") (pin "7") (pinfunction "7_7") (pintype "passive"))
    )
    (net (code "155") (name "/VDD3") (class "Default")
      (node (ref "C027") (pin "1") (pinfunction "1_1") (pintype "passive"))
      (node (ref "C028") (pin "1") (pinfunction "1_1") (pintype "passive"))
      (node (ref "C046") (pin "1") (pinfunction "1_1") (pintype "passive"))
      (node (ref "C064") (pin "1") (pinfunction "1_1") (pintype "passive"))
      (node (ref "C065") (pin "1") (pinfunction "1_1") (pintype "passive"))
      (node (ref "IC4") (pin "2") (pinfunction "VO_2") (pintype "passive"))
      (node (ref "U011") (pin "1") (pinfunction "VCC_1") (pintype "bidirectional"))
      (node (ref "U012") (pin "1") (pinfunction "VCC_1") (pintype "bidirectional"))
      (node (ref "U013") (pin "1") (pinfunction "VCC_1") (pintype "bidirectional"))
      (node (ref "U014") (pin "1") (pinfunction "VCC_1") (pintype "bidirectional"))
      (node (ref "X010") (pin "7") (pinfunction "7_7") (pintype "passive"))
    )
    (net (code "156") (name "/VDD4") (class "Default")
      (node (ref "C029") (pin "1") (pinfunction "1_1") (pintype "passive"))
      (node (ref "C030") (pin "1") (pinfunction "1_1") (pintype "passive"))
      (node (ref "C048") (pin "1") (pinfunction "1_1") (pintype "passive"))
      (node (ref "C066") (pin "1") (pinfunction "1_1") (pintype "passive"))
      (node (ref "C067") (pin "1") (pinfunction "1_1") (pintype "passive"))
      (node (ref "IC5") (pin "2") (pinfunction "VO_2") (pintype "passive"))
      (node (ref "U015") (pin "1") (pinfunction "VCC_1") (pintype "bidirectional"))
      (node (ref "U016") (pin "1") (pinfunction "VCC_1") (pintype "bidirectional"))
      (node (ref "U034") (pin "1") (pinfunction "VCC_1") (pintype "bidirectional"))
      (node (ref "U035") (pin "1") (pinfunction "VCC_1") (pintype "bidirectional"))
      (node (ref "X013") (pin "7") (pinfunction "7_7") (pintype "passive"))
    )
    (net (code "157") (name "/VDD5") (class "Default")
      (node (ref "C031") (pin "1") (pinfunction "1_1") (pintype "passive"))
      (node (ref "C032") (pin "1") (pinfunction "1_1") (pintype "passive"))
      (node (ref "C050") (pin "1") (pinfunction "1_1") (pintype "passive"))
      (node (ref "C068") (pin "1") (pinfunction "1_1") (pintype "passive"))
      (node (ref "C069") (pin "1") (pinfunction "1_1") (pintype "passive"))
      (node (ref "IC6") (pin "2") (pinfunction "VO_2") (pintype "passive"))
      (node (ref "U017") (pin "1") (pinfunction "VCC_1") (pintype "bidirectional"))
      (node (ref "U018") (pin "1") (pinfunction "VCC_1") (pintype "bidirectional"))
      (node (ref "U036") (pin "1") (pinfunction "VCC_1") (pintype "bidirectional"))
      (node (ref "U037") (pin "1") (pinfunction "VCC_1") (pintype "bidirectional"))
      (node (ref "X016") (pin "7") (pinfunction "7_7") (pintype "passive"))
    )
    (net (code "158") (name "/VDD6") (class "Default")
      (node (ref "C033") (pin "1") (pinfunction "1_1") (pintype "passive"))
      (node (ref "C034") (pin "1") (pinfunction "1_1") (pintype "passive"))
      (node (ref "C052") (pin "1") (pinfunction "1_1") (pintype "passive"))
      (node (ref "C070") (pin "1") (pinfunction "1_1") (pintype "passive"))
      (node (ref "C071") (pin "1") (pinfunction "1_1") (pintype "passive"))
      (node (ref "IC7") (pin "2") (pinfunction "VO_2") (pintype "passive"))
      (node (ref "U019") (pin "1") (pinfunction "VCC_1") (pintype "bidirectional"))
      (node (ref "U020") (pin "1") (pinfunction "VCC_1") (pintype "bidirectional"))
      (node (ref "U038") (pin "1") (pinfunction "VCC_1") (pintype "bidirectional"))
      (node (ref "U039") (pin "1") (pinfunction "VCC_1") (pintype "bidirectional"))
      (node (ref "X019") (pin "7") (pinfunction "7_7") (pintype "passive"))
    )
    (net (code "159") (name "/VDD7") (class "Default")
      (node (ref "C036") (pin "1") (pinfunction "1_1") (pintype "passive"))
      (node (ref "C037") (pin "1") (pinfunction "1_1") (pintype "passive"))
      (node (ref "C054") (pin "1") (pinfunction "1_1") (pintype "passive"))
      (node (ref "C072") (pin "1") (pinfunction "1_1") (pintype "passive"))
      (node (ref "C073") (pin "1") (pinfunction "1_1") (pintype "passive"))
      (node (ref "IC8") (pin "2") (pinfunction "VO_2") (pintype "passive"))
      (node (ref "U021") (pin "1") (pinfunction "VCC_1") (pintype "bidirectional"))
      (node (ref "U022") (pin "1") (pinfunction "VCC_1") (pintype "bidirectional"))
      (node (ref "U040") (pin "1") (pinfunction "VCC_1") (pintype "bidirectional"))
      (node (ref "U041") (pin "1") (pinfunction "VCC_1") (pintype "bidirectional"))
      (node (ref "X022") (pin "7") (pinfunction "7_7") (pintype "passive"))
    )
    (net (code "160") (name "GND") (class "Default")
      (node (ref "C000") (pin "2") (pinfunction "2_2") (pintype "passive"))
      (node (ref "C001") (pin "2") (pinfunction "2_2") (pintype "passive"))
      (node (ref "C002") (pin "2") (pinfunction "2_2") (pintype "passive"))
      (node (ref "C003") (pin "2") (pinfunction "2_2") (pintype "passive"))
      (node (ref "C004") (pin "2") (pinfunction "2_2") (pintype "passive"))
      (node (ref "C005") (pin "2") (pinfunction "2_2") (pintype "passive"))
      (node (ref "C006") (pin "2") (pinfunction "2_2") (pintype "passive"))
      (node (ref "C007") (pin "2") (pinfunction "2_2") (pintype "passive"))
      (node (ref "C008") (pin "2") (pinfunction "2_2") (pintype "passive"))
      (node (ref "C009") (pin "2") (pinfunction "2_2") (pintype "passive"))
      (node (ref "C010") (pin "2") (pinfunction "2_2") (pintype "passive"))
      (node (ref "C011") (pin "2") (pinfunction "2_2") (pintype "passive"))
      (node (ref "C012") (pin "2") (pinfunction "2_2") (pintype "passive"))
      (node (ref "C013") (pin "2") (pinfunction "2_2") (pintype "passive"))
      (node (ref "C014") (pin "2") (pinfunction "2_2") (pintype "passive"))
      (node (ref "C015") (pin "2") (pinfunction "2_2") (pintype "passive"))
      (node (ref "C016") (pin "2") (pinfunction "2_2") (pintype "passive"))
      (node (ref "C017") (pin "2") (pinfunction "2_2") (pintype "passive"))
      (node (ref "C018") (pin "2") (pinfunction "2_2") (pintype "passive"))
      (node (ref "C019") (pin "2") (pinfunction "2_2") (pintype "passive"))
      (node (ref "C020") (pin "2") (pinfunction "2_2") (pintype "passive"))
      (node (ref "C021") (pin "2") (pinfunction "2_2") (pintype "passive"))
      (node (ref "C022") (pin "2") (pinfunction "2_2") (pintype "passive"))
      (node (ref "C023") (pin "2") (pinfunction "2_2") (pintype "passive"))
      (node (ref "C024") (pin "2") (pinfunction "2_2") (pintype "passive"))
      (node (ref "C025") (pin "2") (pinfunction "2_2") (pintype "passive"))
      (node (ref "C026") (pin "2") (pinfunction "2_2") (pintype "passive"))
      (node (ref "C027") (pin "2") (pinfunction "2_2") (pintype "passive"))
      (node (ref "C028") (pin "2") (pinfunction "2_2") (pintype "passive"))
      (node (ref "C029") (pin "2") (pinfunction "2_2") (pintype "passive"))
      (node (ref "C030") (pin "2") (pinfunction "2_2") (pintype "passive"))
      (node (ref "C031") (pin "2") (pinfunction "2_2") (pintype "passive"))
      (node (ref "C032") (pin "2") (pinfunction "2_2") (pintype "passive"))
      (node (ref "C033") (pin "2") (pinfunction "2_2") (pintype "passive"))
      (node (ref "C034") (pin "2") (pinfunction "2_2") (pintype "passive"))
      (node (ref "C036") (pin "2") (pinfunction "2_2") (pintype "passive"))
      (node (ref "C037") (pin "2") (pinfunction "2_2") (pintype "passive"))
      (node (ref "C039") (pin "2") (pinfunction "2_2") (pintype "passive"))
      (node (ref "C040") (pin "2") (pinfunction "2_2") (pintype "passive"))
      (node (ref "C041") (pin "2") (pinfunction "2_2") (pintype "passive"))
      (node (ref "C042") (pin "2") (pinfunction "2_2") (pintype "passive"))
      (node (ref "C043") (pin "2") (pinfunction "2_2") (pintype "passive"))
      (node (ref "C044") (pin "2") (pinfunction "2_2") (pintype "passive"))
      (node (ref "C045") (pin "2") (pinfunction "2_2") (pintype "passive"))
      (node (ref "C046") (pin "2") (pinfunction "2_2") (pintype "passive"))
      (node (ref "C047") (pin "2") (pinfunction "2_2") (pintype "passive"))
      (node (ref "C048") (pin "2") (pinfunction "2_2") (pintype "passive"))
      (node (ref "C049") (pin "2") (pinfunction "2_2") (pintype "passive"))
      (node (ref "C050") (pin "2") (pinfunction "2_2") (pintype "passive"))
      (node (ref "C051") (pin "2") (pinfunction "2_2") (pintype "passive"))
      (node (ref "C052") (pin "2") (pinfunction "2_2") (pintype "passive"))
      (node (ref "C053") (pin "2") (pinfunction "2_2") (pintype "passive"))
      (node (ref "C054") (pin "2") (pinfunction "2_2") (pintype "passive"))
      (node (ref "C055") (pin "2") (pinfunction "2_2") (pintype "passive"))
      (node (ref "C056") (pin "2") (pinfunction "2_2") (pintype "passive"))
      (node (ref "C057") (pin "2") (pinfunction "2_2") (pintype "passive"))
      (node (ref "C058") (pin "2") (pinfunction "2_2") (pintype "passive"))
      (node (ref "C059") (pin "2") (pinfunction "2_2") (pintype "passive"))
      (node (ref "C060") (pin "2") (pinfunction "2_2") (pintype "passive"))
      (node (ref "C061") (pin "2") (pinfunction "2_2") (pintype "passive"))
      (node (ref "C062") (pin "2") (pinfunction "2_2") (pintype "passive"))
      (node (ref "C063") (pin "2") (pinfunction "2_2") (pintype "passive"))
      (node (ref "C064") (pin "2") (pinfunction "2_2") (pintype "passive"))
      (node (ref "C065") (pin "2") (pinfunction "2_2") (pintype "passive"))
      (node (ref "C066") (pin "2") (pinfunction "2_2") (pintype "passive"))
      (node (ref "C067") (pin "2") (pinfunction "2_2") (pintype "passive"))
      (node (ref "C068") (pin "2") (pinfunction "2_2") (pintype "passive"))
      (node (ref "C069") (pin "2") (pinfunction "2_2") (pintype "passive"))
      (node (ref "C070") (pin "2") (pinfunction "2_2") (pintype "passive"))
      (node (ref "C071") (pin "2") (pinfunction "2_2") (pintype "passive"))
      (node (ref "C072") (pin "2") (pinfunction "2_2") (pintype "passive"))
      (node (ref "C073") (pin "2") (pinfunction "2_2") (pintype "passive"))
      (node (ref "C074") (pin "2") (pinfunction "2_2") (pintype "passive"))
      (node (ref "C075") (pin "2") (pinfunction "2_2") (pintype "passive"))
      (node (ref "C35") (pin "2") (pinfunction "2_2") (pintype "passive"))
      (node (ref "C800") (pin "2") (pinfunction "2_2") (pintype "passive"))
      (node (ref "C801") (pin "2") (pinfunction "2_2") (pintype "passive"))
      (node (ref "C802") (pin "2") (pinfunction "2_2") (pintype "passive"))
      (node (ref "C820") (pin "2") (pinfunction "2_2") (pintype "passive"))
      (node (ref "C821") (pin "2") (pinfunction "2_2") (pintype "passive"))
      (node (ref "C822") (pin "2") (pinfunction "2_2") (pintype "passive"))
      (node (ref "IC1") (pin "3") (pinfunction "GND_3") (pintype "passive"))
      (node (ref "IC10") (pin "4") (pinfunction "~{E1}_4") (pintype "input"))
      (node (ref "IC10") (pin "5") (pinfunction "~{E2}_5") (pintype "input"))
      (node (ref "IC10") (pin "8") (pinfunction "GND_8") (pintype "power_in"))
      (node (ref "IC11") (pin "7") (pinfunction "G_7") (pintype "input"))
      (node (ref "IC11") (pin "8") (pinfunction "GND_8") (pintype "power_in"))
      (node (ref "IC12") (pin "7") (pinfunction "G_7") (pintype "input"))
      (node (ref "IC12") (pin "8") (pinfunction "GND_8") (pintype "power_in"))
      (node (ref "IC2") (pin "3") (pinfunction "GND_3") (pintype "passive"))
      (node (ref "IC3") (pin "3") (pinfunction "GND_3") (pintype "passive"))
      (node (ref "IC4") (pin "3") (pinfunction "GND_3") (pintype "passive"))
      (node (ref "IC5") (pin "3") (pinfunction "GND_3") (pintype "passive"))
      (node (ref "IC6") (pin "3") (pinfunction "GND_3") (pintype "passive"))
      (node (ref "IC7") (pin "3") (pinfunction "GND_3") (pintype "passive"))
      (node (ref "IC8") (pin "3") (pinfunction "GND_3") (pintype "passive"))
      (node (ref "IC9") (pin "3") (pinfunction "GND_3") (pintype "passive"))
      (node (ref "R002") (pin "1") (pinfunction "1_1") (pintype "passive"))
      (node (ref "R800") (pin "1") (pinfunction "1_1") (pintype "passive"))
      (node (ref "U001") (pin "4") (pinfunction "GND_4") (pintype "bidirectional"))
      (node (ref "U002") (pin "3") (pinfunction "VEE_3") (pintype "power_in"))
      (node (ref "U003") (pin "2") (pinfunction "GND_2") (pintype "power_in"))
      (node (ref "U004") (pin "2") (pinfunction "GND_2") (pintype "power_in"))
      (node (ref "U005") (pin "2") (pinfunction "GND_2") (pintype "power_in"))
      (node (ref "U006") (pin "2") (pinfunction "GND_2") (pintype "power_in"))
      (node (ref "U007") (pin "2") (pinfunction "GND_2") (pintype "power_in"))
      (node (ref "U008") (pin "2") (pinfunction "GND_2") (pintype "power_in"))
      (node (ref "U009") (pin "4") (pinfunction "GND_4") (pintype "bidirectional"))
      (node (ref "U010") (pin "4") (pinfunction "GND_4") (pintype "bidirectional"))
      (node (ref "U011") (pin "4") (pinfunction "GND_4") (pintype "bidirectional"))
      (node (ref "U012") (pin "4") (pinfunction "GND_4") (pintype "bidirectional"))
      (node (ref "U013") (pin "4") (pinfunction "GND_4") (pintype "bidirectional"))
      (node (ref "U014") (pin "4") (pinfunction "GND_4") (pintype "bidirectional"))
      (node (ref "U015") (pin "4") (pinfunction "GND_4") (pintype "bidirectional"))
      (node (ref "U016") (pin "4") (pinfunction "GND_4") (pintype "bidirectional"))
      (node (ref "U017") (pin "4") (pinfunction "GND_4") (pintype "bidirectional"))
      (node (ref "U018") (pin "4") (pinfunction "GND_4") (pintype "bidirectional"))
      (node (ref "U019") (pin "4") (pinfunction "GND_4") (pintype "bidirectional"))
      (node (ref "U020") (pin "4") (pinfunction "GND_4") (pintype "bidirectional"))
      (node (ref "U021") (pin "4") (pinfunction "GND_4") (pintype "bidirectional"))
      (node (ref "U022") (pin "4") (pinfunction "GND_4") (pintype "bidirectional"))
      (node (ref "U024") (pin "10") (pinfunction "GND_10") (pintype "power_in"))
      (node (ref "U024") (pin "19") (pinfunction "G_19") (pintype "input"))
      (node (ref "U025") (pin "4") (pinfunction "GND_4") (pintype "bidirectional"))
      (node (ref "U026") (pin "4") (pinfunction "GND_4") (pintype "bidirectional"))
      (node (ref "U027") (pin "4") (pinfunction "GND_4") (pintype "bidirectional"))
      (node (ref "U028") (pin "4") (pinfunction "GND_4") (pintype "bidirectional"))
      (node (ref "U029") (pin "4") (pinfunction "GND_4") (pintype "bidirectional"))
      (node (ref "U030") (pin "4") (pinfunction "GND_4") (pintype "bidirectional"))
      (node (ref "U031") (pin "4") (pinfunction "GND_4") (pintype "bidirectional"))
      (node (ref "U032") (pin "4") (pinfunction "GND_4") (pintype "bidirectional"))
      (node (ref "U033") (pin "4") (pinfunction "GND_4") (pintype "bidirectional"))
      (node (ref "U034") (pin "4") (pinfunction "GND_4") (pintype "bidirectional"))
      (node (ref "U035") (pin "4") (pinfunction "GND_4") (pintype "bidirectional"))
      (node (ref "U036") (pin "4") (pinfunction "GND_4") (pintype "bidirectional"))
      (node (ref "U037") (pin "4") (pinfunction "GND_4") (pintype "bidirectional"))
      (node (ref "U038") (pin "4") (pinfunction "GND_4") (pintype "bidirectional"))
      (node (ref "U039") (pin "4") (pinfunction "GND_4") (pintype "bidirectional"))
      (node (ref "U040") (pin "4") (pinfunction "GND_4") (pintype "bidirectional"))
      (node (ref "U041") (pin "4") (pinfunction "GND_4") (pintype "bidirectional"))
      (node (ref "U800") (pin "3") (pinfunction "VEE_3") (pintype "power_in"))
      (node (ref "U820") (pin "2") (pinfunction "GND_2") (pintype "power_in"))
      (node (ref "X000") (pin "8") (pinfunction "8_8") (pintype "passive"))
      (node (ref "X000") (pin "G1") (pinfunction "S_G1") (pintype "passive"))
      (node (ref "X000") (pin "G2") (pinfunction "S_G2") (pintype "passive"))
      (node (ref "X001") (pin "G1") (pinfunction "S_G1") (pintype "passive"))
      (node (ref "X001") (pin "G2") (pinfunction "S_G2") (pintype "passive"))
      (node (ref "X003") (pin "1") (pinfunction "P_1") (pintype "passive"))
      (node (ref "X004") (pin "8") (pinfunction "8_8") (pintype "passive"))
      (node (ref "X004") (pin "G1") (pinfunction "S_G1") (pintype "passive"))
      (node (ref "X004") (pin "G2") (pinfunction "S_G2") (pintype "passive"))
      (node (ref "X005") (pin "G1") (pinfunction "S_G1") (pintype "passive"))
      (node (ref "X005") (pin "G2") (pinfunction "S_G2") (pintype "passive"))
      (node (ref "X007") (pin "8") (pinfunction "8_8") (pintype "passive"))
      (node (ref "X007") (pin "G1") (pinfunction "S_G1") (pintype "passive"))
      (node (ref "X007") (pin "G2") (pinfunction "S_G2") (pintype "passive"))
      (node (ref "X008") (pin "G1") (pinfunction "S_G1") (pintype "passive"))
      (node (ref "X008") (pin "G2") (pinfunction "S_G2") (pintype "passive"))
      (node (ref "X010") (pin "8") (pinfunction "8_8") (pintype "passive"))
      (node (ref "X010") (pin "G1") (pinfunction "S_G1") (pintype "passive"))
      (node (ref "X010") (pin "G2") (pinfunction "S_G2") (pintype "passive"))
      (node (ref "X011") (pin "G1") (pinfunction "S_G1") (pintype "passive"))
      (node (ref "X011") (pin "G2") (pinfunction "S_G2") (pintype "passive"))
      (node (ref "X013") (pin "8") (pinfunction "8_8") (pintype "passive"))
      (node (ref "X013") (pin "G1") (pinfunction "S_G1") (pintype "passive"))
      (node (ref "X013") (pin "G2") (pinfunction "S_G2") (pintype "passive"))
      (node (ref "X014") (pin "G1") (pinfunction "S_G1") (pintype "passive"))
      (node (ref "X014") (pin "G2") (pinfunction "S_G2") (pintype "passive"))
      (node (ref "X016") (pin "8") (pinfunction "8_8") (pintype "passive"))
      (node (ref "X016") (pin "G1") (pinfunction "S_G1") (pintype "passive"))
      (node (ref "X016") (pin "G2") (pinfunction "S_G2") (pintype "passive"))
      (node (ref "X017") (pin "G1") (pinfunction "S_G1") (pintype "passive"))
      (node (ref "X017") (pin "G2") (pinfunction "S_G2") (pintype "passive"))
      (node (ref "X019") (pin "8") (pinfunction "8_8") (pintype "passive"))
      (node (ref "X019") (pin "G1") (pinfunction "S_G1") (pintype "passive"))
      (node (ref "X019") (pin "G2") (pinfunction "S_G2") (pintype "passive"))
      (node (ref "X020") (pin "G1") (pinfunction "S_G1") (pintype "passive"))
      (node (ref "X020") (pin "G2") (pinfunction "S_G2") (pintype "passive"))
      (node (ref "X022") (pin "8") (pinfunction "8_8") (pintype "passive"))
      (node (ref "X022") (pin "G1") (pinfunction "S_G1") (pintype "passive"))
      (node (ref "X022") (pin "G2") (pinfunction "S_G2") (pintype "passive"))
      (node (ref "X023") (pin "G1") (pinfunction "S_G1") (pintype "passive"))
      (node (ref "X023") (pin "G2") (pinfunction "S_G2") (pintype "passive"))
    )
    (net (code "161") (name "Net-(U002-VCC)") (class "Default")
      (node (ref "C002") (pin "1") (pinfunction "1_1") (pintype "passive"))
      (node (ref "C004") (pin "1") (pinfunction "1_1") (pintype "passive"))
      (node (ref "L1") (pin "1") (pinfunction "1_1") (pintype "passive"))
      (node (ref "U002") (pin "1") (pinfunction "VCC_1") (pintype "power_in"))
    )
    (net (code "162") (name "Net-(U003-VCC)") (class "Default")
      (node (ref "C005") (pin "1") (pinfunction "1_1") (pintype "passive"))
      (node (ref "C007") (pin "1") (pinfunction "1_1") (pintype "passive"))
      (node (ref "L2") (pin "1") (pinfunction "1_1") (pintype "passive"))
      (node (ref "U003") (pin "3") (pinfunction "VCC_3") (pintype "power_in"))
    )
    (net (code "163") (name "Net-(U004-VCC)") (class "Default")
      (node (ref "C008") (pin "1") (pinfunction "1_1") (pintype "passive"))
      (node (ref "C010") (pin "1") (pinfunction "1_1") (pintype "passive"))
      (node (ref "L3") (pin "1") (pinfunction "1_1") (pintype "passive"))
      (node (ref "U004") (pin "3") (pinfunction "VCC_3") (pintype "power_in"))
    )
    (net (code "164") (name "Net-(U005-VCC)") (class "Default")
      (node (ref "C011") (pin "1") (pinfunction "1_1") (pintype "passive"))
      (node (ref "C013") (pin "1") (pinfunction "1_1") (pintype "passive"))
      (node (ref "L4") (pin "1") (pinfunction "1_1") (pintype "passive"))
      (node (ref "U005") (pin "3") (pinfunction "VCC_3") (pintype "power_in"))
    )
    (net (code "165") (name "Net-(U006-VCC)") (class "Default")
      (node (ref "C014") (pin "1") (pinfunction "1_1") (pintype "passive"))
      (node (ref "C016") (pin "1") (pinfunction "1_1") (pintype "passive"))
      (node (ref "L5") (pin "1") (pinfunction "1_1") (pintype "passive"))
      (node (ref "U006") (pin "3") (pinfunction "VCC_3") (pintype "power_in"))
    )
    (net (code "166") (name "Net-(U007-VCC)") (class "Default")
      (node (ref "C017") (pin "1") (pinfunction "1_1") (pintype "passive"))
      (node (ref "C019") (pin "1") (pinfunction "1_1") (pintype "passive"))
      (node (ref "L6") (pin "1") (pinfunction "1_1") (pintype "passive"))
      (node (ref "U007") (pin "3") (pinfunction "VCC_3") (pintype "power_in"))
    )
    (net (code "167") (name "Net-(U008-VCC)") (class "Default")
      (node (ref "C020") (pin "1") (pinfunction "1_1") (pintype "passive"))
      (node (ref "C022") (pin "1") (pinfunction "1_1") (pintype "passive"))
      (node (ref "L7") (pin "1") (pinfunction "1_1") (pintype "passive"))
      (node (ref "U008") (pin "3") (pinfunction "VCC_3") (pintype "power_in"))
    )
    (net (code "168") (name "Net-(U800-VCC)") (class "Default")
      (node (ref "C800") (pin "1") (pinfunction "1_1") (pintype "passive"))
      (node (ref "C801") (pin "1") (pinfunction "1_1") (pintype "passive"))
      (node (ref "L800") (pin "1") (pinfunction "1_1") (pintype "passive"))
      (node (ref "U800") (pin "1") (pinfunction "VCC_1") (pintype "power_in"))
    )
    (net (code "169") (name "Net-(U820-VCC)") (class "Default")
      (node (ref "C820") (pin "1") (pinfunction "1_1") (pintype "passive"))
      (node (ref "C821") (pin "1") (pinfunction "1_1") (pintype "passive"))
      (node (ref "L820") (pin "1") (pinfunction "1_1") (pintype "passive"))
      (node (ref "U820") (pin "3") (pinfunction "VCC_3") (pintype "power_in"))
    )
    (net (code "170") (name "unconnected-(IC11A-W-Pad6)") (class "Default")
      (node (ref "IC11") (pin "6") (pinfunction "W_6") (pintype "output"))
    )
    (net (code "171") (name "unconnected-(IC12A-W-Pad6)") (class "Default")
      (node (ref "IC12") (pin "6") (pinfunction "W_6") (pintype "output"))
    )
    (net (code "172") (name "unconnected-(U001-INB-Pad3)") (class "Default")
      (node (ref "U001") (pin "3") (pinfunction "INB_3") (pintype "bidirectional"))
    )
    (net (code "173") (name "unconnected-(U001-OUTB1-Pad6)") (class "Default")
      (node (ref "U001") (pin "6") (pinfunction "OUTB1_6") (pintype "bidirectional"))
    )
    (net (code "174") (name "unconnected-(U001-OUTB2-Pad5)") (class "Default")
      (node (ref "U001") (pin "5") (pinfunction "OUTB2_5") (pintype "bidirectional"))
    )
    (net (code "175") (name "unconnected-(U011-INB-Pad3)") (class "Default")
      (node (ref "U011") (pin "3") (pinfunction "INB_3") (pintype "bidirectional"))
    )
    (net (code "176") (name "unconnected-(U011-OUTB1-Pad6)") (class "Default")
      (node (ref "U011") (pin "6") (pinfunction "OUTB1_6") (pintype "bidirectional"))
    )
    (net (code "177") (name "unconnected-(U011-OUTB2-Pad5)") (class "Default")
      (node (ref "U011") (pin "5") (pinfunction "OUTB2_5") (pintype "bidirectional"))
    )
    (net (code "178") (name "unconnected-(U015-INB-Pad3)") (class "Default")
      (node (ref "U015") (pin "3") (pinfunction "INB_3") (pintype "bidirectional"))
    )
    (net (code "179") (name "unconnected-(U015-OUTB1-Pad6)") (class "Default")
      (node (ref "U015") (pin "6") (pinfunction "OUTB1_6") (pintype "bidirectional"))
    )
    (net (code "180") (name "unconnected-(U015-OUTB2-Pad5)") (class "Default")
      (node (ref "U015") (pin "5") (pinfunction "OUTB2_5") (pintype "bidirectional"))
    )
    (net (code "181") (name "unconnected-(U017-INB-Pad3)") (class "Default")
      (node (ref "U017") (pin "3") (pinfunction "INB_3") (pintype "bidirectional"))
    )
    (net (code "182") (name "unconnected-(U017-OUTB1-Pad6)") (class "Default")
      (node (ref "U017") (pin "6") (pinfunction "OUTB1_6") (pintype "bidirectional"))
    )
    (net (code "183") (name "unconnected-(U017-OUTB2-Pad5)") (class "Default")
      (node (ref "U017") (pin "5") (pinfunction "OUTB2_5") (pintype "bidirectional"))
    )
    (net (code "184") (name "unconnected-(U019-INB-Pad3)") (class "Default")
      (node (ref "U019") (pin "3") (pinfunction "INB_3") (pintype "bidirectional"))
    )
    (net (code "185") (name "unconnected-(U019-OUTB1-Pad6)") (class "Default")
      (node (ref "U019") (pin "6") (pinfunction "OUTB1_6") (pintype "bidirectional"))
    )
    (net (code "186") (name "unconnected-(U019-OUTB2-Pad5)") (class "Default")
      (node (ref "U019") (pin "5") (pinfunction "OUTB2_5") (pintype "bidirectional"))
    )
    (net (code "187") (name "unconnected-(U021-INB-Pad3)") (class "Default")
      (node (ref "U021") (pin "3") (pinfunction "INB_3") (pintype "bidirectional"))
    )
    (net (code "188") (name "unconnected-(U021-OUTB1-Pad6)") (class "Default")
      (node (ref "U021") (pin "6") (pinfunction "OUTB1_6") (pintype "bidirectional"))
    )
    (net (code "189") (name "unconnected-(U021-OUTB2-Pad5)") (class "Default")
      (node (ref "U021") (pin "5") (pinfunction "OUTB2_5") (pintype "bidirectional"))
    )
    (net (code "190") (name "unconnected-(U024A-G-Pad1)") (class "Default")
      (node (ref "U024") (pin "1") (pinfunction "G_1") (pintype "input"))
    )
    (net (code "191") (name "unconnected-(U024B-A1-Pad11)") (class "Default")
      (node (ref "U024") (pin "11") (pinfunction "A1_11") (pintype "input"))
    )
    (net (code "192") (name "unconnected-(U024B-A2-Pad13)") (class "Default")
      (node (ref "U024") (pin "13") (pinfunction "A2_13") (pintype "input"))
    )
    (net (code "193") (name "unconnected-(U024B-A3-Pad15)") (class "Default")
      (node (ref "U024") (pin "15") (pinfunction "A3_15") (pintype "input"))
    )
    (net (code "194") (name "unconnected-(U024B-A4-Pad17)") (class "Default")
      (node (ref "U024") (pin "17") (pinfunction "A4_17") (pintype "input"))
    )
    (net (code "195") (name "unconnected-(U024B-Y1-Pad9)") (class "Default")
      (node (ref "U024") (pin "9") (pinfunction "Y1_9") (pintype "tri_state"))
    )
    (net (code "196") (name "unconnected-(U024B-Y2-Pad7)") (class "Default")
      (node (ref "U024") (pin "7") (pinfunction "Y2_7") (pintype "tri_state"))
    )
    (net (code "197") (name "unconnected-(U024B-Y3-Pad5)") (class "Default")
      (node (ref "U024") (pin "5") (pinfunction "Y3_5") (pintype "tri_state"))
    )
    (net (code "198") (name "unconnected-(U024B-Y4-Pad3)") (class "Default")
      (node (ref "U024") (pin "3") (pinfunction "Y4_3") (pintype "tri_state"))
    )
    (net (code "199") (name "unconnected-(U025-INB-Pad3)") (class "Default")
      (node (ref "U025") (pin "3") (pinfunction "INB_3") (pintype "bidirectional"))
    )
    (net (code "200") (name "unconnected-(U025-OUTB1-Pad6)") (class "Default")
      (node (ref "U025") (pin "6") (pinfunction "OUTB1_6") (pintype "bidirectional"))
    )
    (net (code "201") (name "unconnected-(U025-OUTB2-Pad5)") (class "Default")
      (node (ref "U025") (pin "5") (pinfunction "OUTB2_5") (pintype "bidirectional"))
    )
    (net (code "202") (name "unconnected-(U030-INB-Pad3)") (class "Default")
      (node (ref "U030") (pin "3") (pinfunction "INB_3") (pintype "bidirectional"))
    )
    (net (code "203") (name "unconnected-(U030-OUTB1-Pad6)") (class "Default")
      (node (ref "U030") (pin "6") (pinfunction "OUTB1_6") (pintype "bidirectional"))
    )
    (net (code "204") (name "unconnected-(U030-OUTB2-Pad5)") (class "Default")
      (node (ref "U030") (pin "5") (pinfunction "OUTB2_5") (pintype "bidirectional"))
    )
  )
)
